# auto_turn.net
KiCad netlist of a schematic drawn in Altium Designer
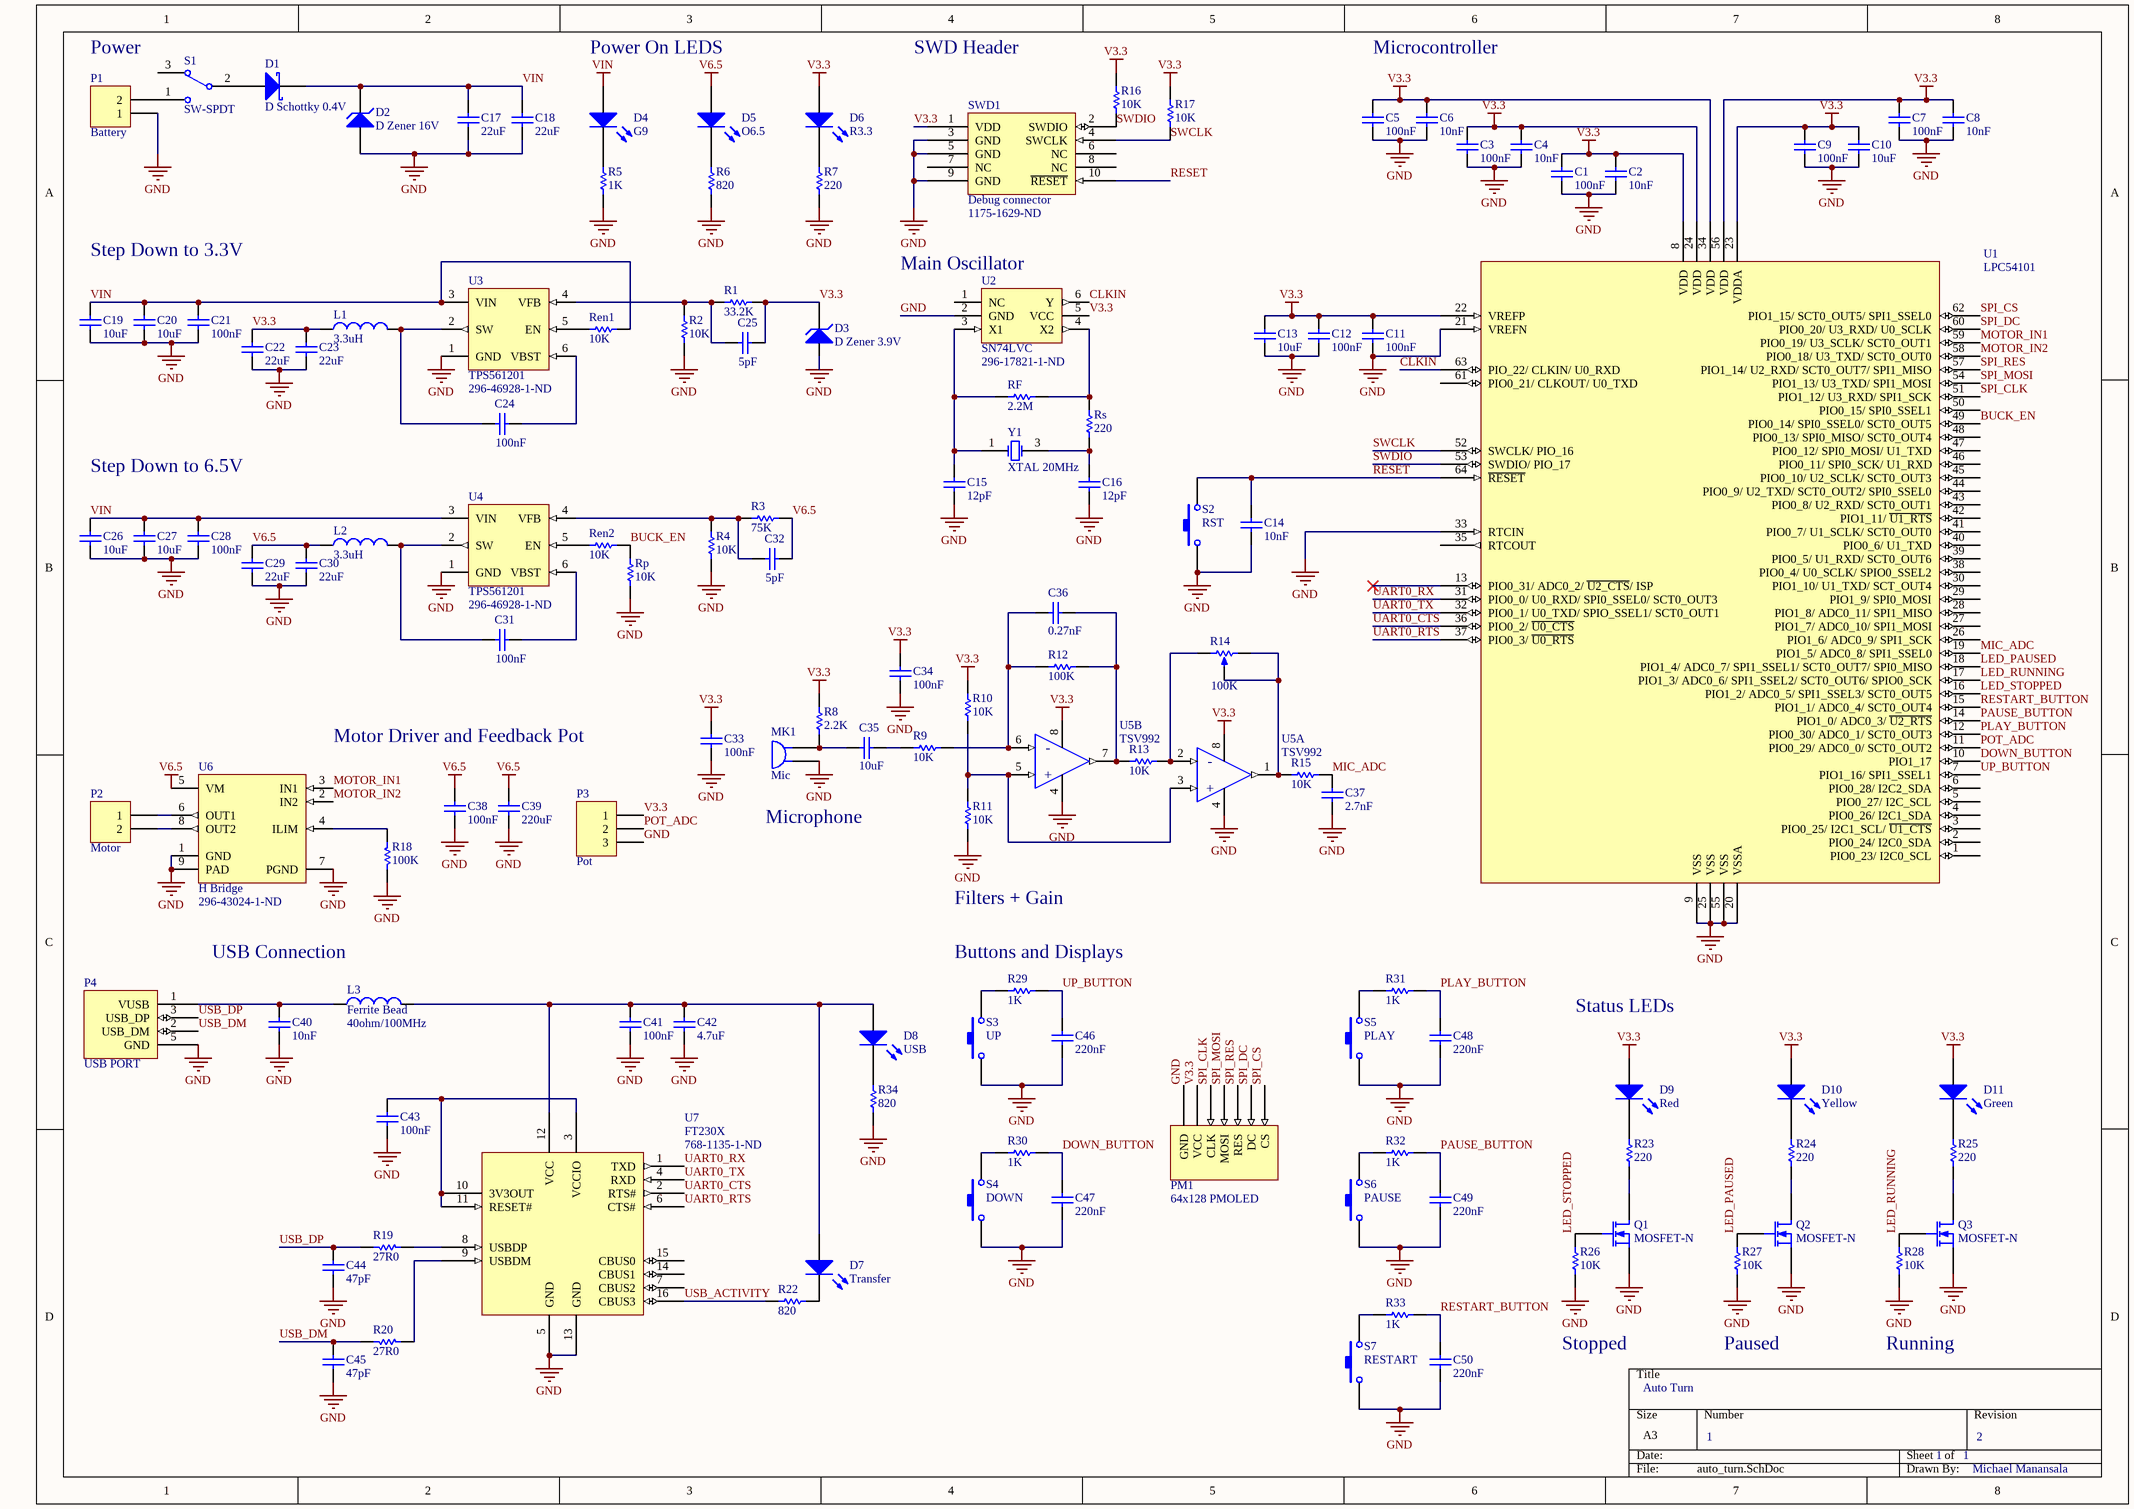
[diagram p0: auto_turn.SchDoc]

(export (version "E")
  (design (tool "Eeschema 10.0.6"))
  (components
    (comp (ref "C1")
      (value "100nF")
      (footprint "0805 MD")
      (description "Capacitor")
      (fields
        (field (name "MANUFACTURER") "Samsung Electro-Mechanics America, Inc.")
        (field (name "MANUFACTURERPARTNUMBER") "CL21B104JBCNNNC")
      )
      (libsource (lib "Miscellaneous Devices") (part "Cap"))
    )
    (comp (ref "C2")
      (value "10nF")
      (footprint "0805 MD")
      (description "Capacitor")
      (fields
        (field (name "MANUFACTURER") "Samsung Electro-Mechanics America, Inc.")
        (field (name "MANUFACTURERPARTNUMBER") "CL21B103JBANNNC")
      )
      (libsource (lib "Miscellaneous Devices") (part "Cap"))
    )
    (comp (ref "C3")
      (value "100nF")
      (footprint "0805 MD")
      (description "Capacitor")
      (fields
        (field (name "MANUFACTURER") "Samsung Electro-Mechanics America, Inc.")
        (field (name "MANUFACTURERPARTNUMBER") "CL21B104JBCNNNC")
      )
      (libsource (lib "Miscellaneous Devices") (part "Cap"))
    )
    (comp (ref "C4")
      (value "10nF")
      (footprint "0805 MD")
      (description "Capacitor")
      (fields
        (field (name "MANUFACTURER") "Samsung Electro-Mechanics America, Inc.")
        (field (name "MANUFACTURERPARTNUMBER") "CL21B103JBANNNC")
      )
      (libsource (lib "Miscellaneous Devices") (part "Cap"))
    )
    (comp (ref "C5")
      (value "100nF")
      (footprint "0805 MD")
      (description "Capacitor")
      (fields
        (field (name "MANUFACTURER") "Samsung Electro-Mechanics America, Inc.")
        (field (name "MANUFACTURERPARTNUMBER") "CL21B104JBCNNNC")
      )
      (libsource (lib "Miscellaneous Devices") (part "Cap"))
    )
    (comp (ref "C6")
      (value "10nF")
      (footprint "0805 MD")
      (description "Capacitor")
      (fields
        (field (name "MANUFACTURER") "Samsung Electro-Mechanics America, Inc.")
        (field (name "MANUFACTURERPARTNUMBER") "CL21B103JBANNNC")
      )
      (libsource (lib "Miscellaneous Devices") (part "Cap"))
    )
    (comp (ref "C7")
      (value "100nF")
      (footprint "0805 MD")
      (description "Capacitor")
      (fields
        (field (name "MANUFACTURER") "Samsung Electro-Mechanics America, Inc.")
        (field (name "MANUFACTURERPARTNUMBER") "CL21B104JBCNNNC")
      )
      (libsource (lib "Miscellaneous Devices") (part "Cap"))
    )
    (comp (ref "C8")
      (value "10nF")
      (footprint "0805 MD")
      (description "Capacitor")
      (fields
        (field (name "MANUFACTURER") "Samsung Electro-Mechanics America, Inc.")
        (field (name "MANUFACTURERPARTNUMBER") "CL21B103JBANNNC")
      )
      (libsource (lib "Miscellaneous Devices") (part "Cap"))
    )
    (comp (ref "C9")
      (value "100nF")
      (footprint "0805 MD")
      (description "Capacitor")
      (fields
        (field (name "MANUFACTURER") "Samsung Electro-Mechanics America, Inc.")
        (field (name "MANUFACTURERPARTNUMBER") "CL21B104JBCNNNC")
      )
      (libsource (lib "Miscellaneous Devices") (part "Cap"))
    )
    (comp (ref "C10")
      (value "10uF")
      (footprint "0805 MD")
      (description "Capacitor")
      (fields
        (field (name "MANUFACTURER") "Samsung Electro-Mechanics America, Inc.")
        (field (name "MANUFACTURERPARTNUMBER") "CL21A106KOCLRNC")
      )
      (libsource (lib "Miscellaneous Devices") (part "Cap"))
    )
    (comp (ref "C11")
      (value "100nF")
      (footprint "0805 MD")
      (description "Capacitor")
      (fields
        (field (name "MANUFACTURER") "Samsung Electro-Mechanics America, Inc.")
        (field (name "MANUFACTURERPARTNUMBER") "CL21B104JBCNNNC")
      )
      (libsource (lib "Miscellaneous Devices") (part "Cap"))
    )
    (comp (ref "C12")
      (value "100nF")
      (footprint "0805 MD")
      (description "Capacitor")
      (fields
        (field (name "MANUFACTURER") "Samsung Electro-Mechanics America, Inc.")
        (field (name "MANUFACTURERPARTNUMBER") "CL21B104JBCNNNC")
      )
      (libsource (lib "Miscellaneous Devices") (part "Cap"))
    )
    (comp (ref "C13")
      (value "10uF")
      (footprint "0805 MD")
      (description "Capacitor")
      (fields
        (field (name "MANUFACTURER") "Samsung Electro-Mechanics America, Inc.")
        (field (name "MANUFACTURERPARTNUMBER") "CL21A106KOCLRNC")
      )
      (libsource (lib "Miscellaneous Devices") (part "Cap"))
    )
    (comp (ref "C14")
      (value "10nF")
      (footprint "0805 MD")
      (description "Capacitor")
      (fields
        (field (name "MANUFACTURER") "Samsung Electro-Mechanics America, Inc.")
        (field (name "MANUFACTURERPARTNUMBER") "CL21B103JBANNNC")
      )
      (libsource (lib "Miscellaneous Devices") (part "Cap"))
    )
    (comp (ref "C15")
      (value "12pF")
      (footprint "0805 MD")
      (description "Capacitor")
      (fields
        (field (name "MANUFACTURER") "Samsung Electro-Mechanics America, Inc.")
        (field (name "MANUFACTURERPARTNUMBER") "CL21C120JBANNNC")
      )
      (libsource (lib "Miscellaneous Devices") (part "Cap"))
    )
    (comp (ref "C16")
      (value "12pF")
      (footprint "0805 MD")
      (description "Capacitor")
      (fields
        (field (name "MANUFACTURER") "Samsung Electro-Mechanics America, Inc.")
        (field (name "MANUFACTURERPARTNUMBER") "CL21C120JBANNNC")
      )
      (libsource (lib "Miscellaneous Devices") (part "Cap"))
    )
    (comp (ref "C17")
      (value "22uF")
      (footprint "0805 MD")
      (description "Capacitor")
      (fields
        (field (name "MANUFACTURER") "Samsung Electro-Mechanics America, Inc.")
        (field (name "MANUFACTURERPARTNUMBER") "CL21A226MOCLRNC")
      )
      (libsource (lib "Miscellaneous Devices") (part "Cap"))
    )
    (comp (ref "C18")
      (value "22uF")
      (footprint "0805 MD")
      (description "Capacitor")
      (fields
        (field (name "MANUFACTURER") "Samsung Electro-Mechanics America, Inc.")
        (field (name "MANUFACTURERPARTNUMBER") "CL21A226MOCLRNC")
      )
      (libsource (lib "Miscellaneous Devices") (part "Cap"))
    )
    (comp (ref "C19")
      (value "10uF")
      (footprint "0805 MD")
      (description "Capacitor")
      (fields
        (field (name "MANUFACTURER") "Samsung Electro-Mechanics America, Inc.")
        (field (name "MANUFACTURERPARTNUMBER") "CL21A106KOCLRNC")
      )
      (libsource (lib "Miscellaneous Devices") (part "Cap"))
    )
    (comp (ref "C20")
      (value "10uF")
      (footprint "0805 MD")
      (description "Capacitor")
      (fields
        (field (name "MANUFACTURER") "Samsung Electro-Mechanics America, Inc.")
        (field (name "MANUFACTURERPARTNUMBER") "CL21A106KOCLRNC")
      )
      (libsource (lib "Miscellaneous Devices") (part "Cap"))
    )
    (comp (ref "C21")
      (value "100nF")
      (footprint "0805 MD")
      (description "Capacitor")
      (fields
        (field (name "MANUFACTURER") "Samsung Electro-Mechanics America, Inc.")
        (field (name "MANUFACTURERPARTNUMBER") "CL21B104JBCNNNC")
      )
      (libsource (lib "Miscellaneous Devices") (part "Cap"))
    )
    (comp (ref "C22")
      (value "22uF")
      (footprint "0805 MD")
      (description "Capacitor")
      (fields
        (field (name "MANUFACTURER") "Samsung Electro-Mechanics America, Inc.")
        (field (name "MANUFACTURERPARTNUMBER") "CL21A226MOCLRNC")
      )
      (libsource (lib "Miscellaneous Devices") (part "Cap"))
    )
    (comp (ref "C23")
      (value "22uF")
      (footprint "0805 MD")
      (description "Capacitor")
      (fields
        (field (name "MANUFACTURER") "Samsung Electro-Mechanics America, Inc.")
        (field (name "MANUFACTURERPARTNUMBER") "CL21A226MOCLRNC")
      )
      (libsource (lib "Miscellaneous Devices") (part "Cap"))
    )
    (comp (ref "C24")
      (value "100nF")
      (footprint "0805 MD")
      (description "Capacitor")
      (fields
        (field (name "MANUFACTURER") "Samsung Electro-Mechanics America, Inc.")
        (field (name "MANUFACTURERPARTNUMBER") "CL21B104JBCNNNC")
      )
      (libsource (lib "Miscellaneous Devices") (part "Cap"))
    )
    (comp (ref "C25")
      (value "5pF")
      (footprint "0805 MD")
      (description "Capacitor")
      (fields
        (field (name "MANUFACTURER") "Samsung Electro-Mechanics America, Inc.")
        (field (name "MANUFACTURERPARTNUMBER") "CL21C050CBANNNC")
      )
      (libsource (lib "Miscellaneous Devices") (part "Cap"))
    )
    (comp (ref "C26")
      (value "10uF")
      (footprint "0805 MD")
      (description "Capacitor")
      (fields
        (field (name "MANUFACTURER") "Samsung Electro-Mechanics America, Inc.")
        (field (name "MANUFACTURERPARTNUMBER") "CL21A106KOCLRNC")
      )
      (libsource (lib "Miscellaneous Devices") (part "Cap"))
    )
    (comp (ref "C27")
      (value "10uF")
      (footprint "0805 MD")
      (description "Capacitor")
      (fields
        (field (name "MANUFACTURER") "Samsung Electro-Mechanics America, Inc.")
        (field (name "MANUFACTURERPARTNUMBER") "CL21A106KOCLRNC")
      )
      (libsource (lib "Miscellaneous Devices") (part "Cap"))
    )
    (comp (ref "C28")
      (value "100nF")
      (footprint "0805 MD")
      (description "Capacitor")
      (fields
        (field (name "MANUFACTURER") "Samsung Electro-Mechanics America, Inc.")
        (field (name "MANUFACTURERPARTNUMBER") "CL21B104JBCNNNC")
      )
      (libsource (lib "Miscellaneous Devices") (part "Cap"))
    )
    (comp (ref "C29")
      (value "22uF")
      (footprint "0805 MD")
      (description "Capacitor")
      (fields
        (field (name "MANUFACTURER") "Samsung Electro-Mechanics America, Inc.")
        (field (name "MANUFACTURERPARTNUMBER") "CL21A226MOCLRNC")
      )
      (libsource (lib "Miscellaneous Devices") (part "Cap"))
    )
    (comp (ref "C30")
      (value "22uF")
      (footprint "0805 MD")
      (description "Capacitor")
      (fields
        (field (name "MANUFACTURER") "Samsung Electro-Mechanics America, Inc.")
        (field (name "MANUFACTURERPARTNUMBER") "CL21A226MOCLRNC")
      )
      (libsource (lib "Miscellaneous Devices") (part "Cap"))
    )
    (comp (ref "C31")
      (value "100nF")
      (footprint "0805 MD")
      (description "Capacitor")
      (fields
        (field (name "MANUFACTURER") "Samsung Electro-Mechanics America, Inc.")
        (field (name "MANUFACTURERPARTNUMBER") "CL21B104JBCNNNC")
      )
      (libsource (lib "Miscellaneous Devices") (part "Cap"))
    )
    (comp (ref "C32")
      (value "5pF")
      (footprint "0805 MD")
      (description "Capacitor")
      (fields
        (field (name "MANUFACTURER") "Samsung Electro-Mechanics America, Inc.")
        (field (name "MANUFACTURERPARTNUMBER") "CL21C050CBANNNC")
      )
      (libsource (lib "Miscellaneous Devices") (part "Cap"))
    )
    (comp (ref "C33")
      (value "100nF")
      (footprint "0805 MD")
      (description "Capacitor")
      (fields
        (field (name "MANUFACTURER") "Samsung Electro-Mechanics America, Inc.")
        (field (name "MANUFACTURERPARTNUMBER") "CL21B104JBCNNNC")
      )
      (libsource (lib "Miscellaneous Devices") (part "Cap"))
    )
    (comp (ref "C34")
      (value "100nF")
      (footprint "0805 MD")
      (description "Capacitor")
      (fields
        (field (name "MANUFACTURER") "Samsung Electro-Mechanics America, Inc.")
        (field (name "MANUFACTURERPARTNUMBER") "CL21B104JBCNNNC")
      )
      (libsource (lib "Miscellaneous Devices") (part "Cap"))
    )
    (comp (ref "C35")
      (value "10uF")
      (footprint "0805 MD")
      (description "Capacitor")
      (fields
        (field (name "MANUFACTURER") "Samsung Electro-Mechanics America, Inc.")
        (field (name "MANUFACTURERPARTNUMBER") "CL21A106KOCLRNC")
      )
      (libsource (lib "Miscellaneous Devices") (part "Cap"))
    )
    (comp (ref "C36")
      (value "0.27nF")
      (footprint "0805 MD")
      (description "Capacitor")
      (fields
        (field (name "MANUFACTURER") "Samsung Electro-Mechanics America, Inc.")
        (field (name "MANUFACTURERPARTNUMBER") "CL21B271KCANNNC")
      )
      (libsource (lib "Miscellaneous Devices") (part "Cap"))
    )
    (comp (ref "C37")
      (value "2.7nF")
      (footprint "0805 MD")
      (description "Capacitor")
      (fields
        (field (name "MANUFACTURER") "Samsung Electro-Mechanics America, Inc.")
        (field (name "MANUFACTURERPARTNUMBER") "CL21C272JBFNNNE")
      )
      (libsource (lib "Miscellaneous Devices") (part "Cap"))
    )
    (comp (ref "C38")
      (value "100nF")
      (footprint "0805 MD")
      (description "Capacitor")
      (fields
        (field (name "MANUFACTURER") "Samsung Electro-Mechanics America, Inc.")
        (field (name "MANUFACTURERPARTNUMBER") "CL21B104JBCNNNC")
      )
      (libsource (lib "Miscellaneous Devices") (part "Cap"))
    )
    (comp (ref "C39")
      (value "220uF")
      (footprint "RAD-0.1")
      (description "Capacitor")
      (fields (field (name "MANUFACTURER") "Nichicon") (field (name "MANUFACTURERPARTNUMBER") "UVR1C221MED"))
      (libsource (lib "Miscellaneous Devices") (part "Cap"))
    )
    (comp (ref "C40")
      (value "10nF")
      (footprint "0805 MD")
      (description "Capacitor")
      (fields
        (field (name "MANUFACTURER") "Samsung Electro-Mechanics America, Inc.")
        (field (name "MANUFACTURERPARTNUMBER") "CL21B103JBANNNC")
      )
      (libsource (lib "Miscellaneous Devices") (part "Cap"))
    )
    (comp (ref "C41")
      (value "100nF")
      (footprint "0805 MD")
      (description "Capacitor")
      (fields
        (field (name "MANUFACTURER") "Samsung Electro-Mechanics America, Inc.")
        (field (name "MANUFACTURERPARTNUMBER") "CL21B104JBCNNNC")
      )
      (libsource (lib "Miscellaneous Devices") (part "Cap"))
    )
    (comp (ref "C42")
      (value "4.7uF")
      (footprint "0805 MD")
      (description "Capacitor")
      (fields
        (field (name "MANUFACTURER") "Samsung Electro-Mechanics America, Inc.")
        (field (name "MANUFACTURERPARTNUMBER") "CL21A475KQFNNNG")
      )
      (libsource (lib "Miscellaneous Devices") (part "Cap"))
    )
    (comp (ref "C43")
      (value "100nF")
      (footprint "0805 MD")
      (description "Capacitor")
      (fields
        (field (name "MANUFACTURER") "Samsung Electro-Mechanics America, Inc.")
        (field (name "MANUFACTURERPARTNUMBER") "CL21B104JBCNNNC")
      )
      (libsource (lib "Miscellaneous Devices") (part "Cap"))
    )
    (comp (ref "C44")
      (value "47pF")
      (footprint "0805 MD")
      (description "Capacitor")
      (fields
        (field (name "MANUFACTURER") "Samsung Electro-Mechanics America, Inc.")
        (field (name "MANUFACTURERPARTNUMBER") "CL21C470JBANNNC")
      )
      (libsource (lib "Miscellaneous Devices") (part "Cap"))
    )
    (comp (ref "C45")
      (value "47pF")
      (footprint "0805 MD")
      (description "Capacitor")
      (fields
        (field (name "MANUFACTURER") "Samsung Electro-Mechanics America, Inc.")
        (field (name "MANUFACTURERPARTNUMBER") "CL21C470JBANNNC")
      )
      (libsource (lib "Miscellaneous Devices") (part "Cap"))
    )
    (comp (ref "C46")
      (value "220nF")
      (footprint "0805 MD")
      (description "Capacitor")
      (fields
        (field (name "MANUFACTURER") "Samsung Electro-Mechanics America, Inc.")
        (field (name "MANUFACTURERPARTNUMBER") "CL21B224KAFNNNG")
      )
      (libsource (lib "Miscellaneous Devices") (part "Cap"))
    )
    (comp (ref "C47")
      (value "220nF")
      (footprint "0805 MD")
      (description "Capacitor")
      (fields
        (field (name "MANUFACTURER") "Samsung Electro-Mechanics America, Inc.")
        (field (name "MANUFACTURERPARTNUMBER") "CL21B224KAFNNNG")
      )
      (libsource (lib "Miscellaneous Devices") (part "Cap"))
    )
    (comp (ref "C48")
      (value "220nF")
      (footprint "0805 MD")
      (description "Capacitor")
      (fields
        (field (name "MANUFACTURER") "Samsung Electro-Mechanics America, Inc.")
        (field (name "MANUFACTURERPARTNUMBER") "CL21B224KAFNNNG")
      )
      (libsource (lib "Miscellaneous Devices") (part "Cap"))
    )
    (comp (ref "C49")
      (value "220nF")
      (footprint "0805 MD")
      (description "Capacitor")
      (fields
        (field (name "MANUFACTURER") "Samsung Electro-Mechanics America, Inc.")
        (field (name "MANUFACTURERPARTNUMBER") "CL21B224KAFNNNG")
      )
      (libsource (lib "Miscellaneous Devices") (part "Cap"))
    )
    (comp (ref "C50")
      (value "220nF")
      (footprint "0805 MD")
      (description "Capacitor")
      (fields
        (field (name "MANUFACTURER") "Samsung Electro-Mechanics America, Inc.")
        (field (name "MANUFACTURERPARTNUMBER") "CL21B224KAFNNNG")
      )
      (libsource (lib "Miscellaneous Devices") (part "Cap"))
    )
    (comp (ref "D1")
      (value "D Schottky 0.4V")
      (footprint "DO219AB")
      (description "Schottky Diode")
      (fields
        (field (name "MANUFACTURER") "Vishay Semiconductor Diodes Division")
        (field (name "MANUFACTURERPARTNUMBER") "SL02-GS08")
      )
      (libsource (lib "Miscellaneous Devices") (part "D Schottky"))
    )
    (comp (ref "D2")
      (value "D Zener 16V")
      (footprint "DO219AB")
      (description "Zener Diode")
      (fields
        (field (name "MANUFACTURER") "Vishay Semiconductor Diodes Division")
        (field (name "MANUFACTURERPARTNUMBER") "BZD27C16P-E3-08")
      )
      (libsource (lib "Miscellaneous Devices") (part "D Zener"))
    )
    (comp (ref "D3")
      (value "D Zener 3.9V")
      (footprint "DO219AB")
      (description "Zener Diode")
      (fields
        (field (name "MANUFACTURER") "Vishay Semiconductor Diodes Division")
        (field (name "MANUFACTURERPARTNUMBER") "BZD27B3V9P-M3-08")
      )
      (libsource (lib "Miscellaneous Devices") (part "D Zener"))
    )
    (comp (ref "D4")
      (value "G9")
      (footprint "0805 MD")
      (description "LED Green")
      (fields
        (field (name "MANUFACTURER") "Lite-On Inc.")
        (field (name "MANUFACTURERPARTNUMBER") "LTST-C171KGKT")
      )
      (libsource (lib "Miscellaneous Devices") (part "LED1"))
    )
    (comp (ref "D5")
      (value "O6.5")
      (footprint "0805 MD")
      (description "LED Orange")
      (fields
        (field (name "MANUFACTURER") "Lite-On Inc.")
        (field (name "MANUFACTURERPARTNUMBER") "LTST-C170KFKT")
      )
      (libsource (lib "Miscellaneous Devices") (part "LED1"))
    )
    (comp (ref "D6")
      (value "R3.3")
      (footprint "0805 MD")
      (description "LED Red")
      (fields
        (field (name "MANUFACTURER") "Lite-On Inc.")
        (field (name "MANUFACTURERPARTNUMBER") "LTST-C171KRKT")
      )
      (libsource (lib "Miscellaneous Devices") (part "LED1"))
    )
    (comp (ref "D7")
      (value "Transfer")
      (footprint "0805 MD")
      (description "Green LED")
      (fields
        (field (name "MANUFACTURER") "Lite-On Inc.")
        (field (name "MANUFACTURERPARTNUMBER") "LTST-C171KRKT")
      )
      (libsource (lib "Miscellaneous Devices") (part "LED1"))
    )
    (comp (ref "D8")
      (value "USB")
      (footprint "0805 MD")
      (description "LED Green")
      (fields
        (field (name "MANUFACTURER") "Lite-On Inc.")
        (field (name "MANUFACTURERPARTNUMBER") "LTST-C171KGKT")
      )
      (libsource (lib "Miscellaneous Devices") (part "LED1"))
    )
    (comp (ref "D9")
      (value "Red")
      (footprint "5mm LED")
      (description "LED Red")
      (fields (field (name "MANUFACTURER") "Kingbright") (field (name "MANUFACTURERPARTNUMBER") "WP7113ID"))
      (libsource (lib "Miscellaneous Devices") (part "LED1"))
    )
    (comp (ref "D10")
      (value "Yellow")
      (footprint "5mm LED")
      (description "LED Yellow")
      (fields (field (name "MANUFACTURER") "Kingbright") (field (name "MANUFACTURERPARTNUMBER") "WP7113ND"))
      (libsource (lib "Miscellaneous Devices") (part "LED1"))
    )
    (comp (ref "D11")
      (value "Green")
      (footprint "5mm LED")
      (description "LED Green")
      (fields (field (name "MANUFACTURER") "Kingbright") (field (name "MANUFACTURERPARTNUMBER") "WP7113GD"))
      (libsource (lib "Miscellaneous Devices") (part "LED1"))
    )
    (comp (ref "L1")
      (value "3.3uH")
      (footprint "0805 MD")
      (description "Inductor")
      (fields
        (field (name "MANUFACTURER") "Taiyo Yuden")
        (field (name "MANUFACTURERPARTNUMBER") "BRC2012T3R3MD")
      )
      (libsource (lib "Miscellaneous Devices") (part "Inductor"))
    )
    (comp (ref "L2")
      (value "3.3uH")
      (footprint "0805 MD")
      (description "Inductor")
      (fields
        (field (name "MANUFACTURER") "Taiyo Yuden")
        (field (name "MANUFACTURERPARTNUMBER") "BRC2012T3R3MD")
      )
      (libsource (lib "Miscellaneous Devices") (part "Inductor"))
    )
    (comp (ref "L3")
      (value "Ferrite Bead")
      (footprint "0805 MD")
      (description "Inductor")
      (fields
        (field (name "ALTIUM_VALUE") "40ohm/100MHz")
        (field (name "MANUFACTURER") "Laird-Signal Integrity Products")
        (field (name "MANUFACTURERPARTNUMBER") "MI0805K400R-10")
      )
      (libsource (lib "Miscellaneous Devices") (part "Inductor"))
    )
    (comp (ref "MK1")
      (value "Mic")
      (footprint "CMA-4544PF-W")
      (description "Electret Microphone")
      (fields (field (name "MANUFACTURER") "CUI Inc.") (field (name "MANUFACTURERPARTNUMBER") "CMA-4544PF-W"))
      (libsource (lib "Miscellaneous Devices") (part "Mic1"))
    )
    (comp (ref "P1")
      (value "Battery")
      (footprint "HDR1X2")
      (description "Header, 2-Pin")
      (libsource (lib "") (part "Header 2_1"))
    )
    (comp (ref "P2")
      (value "Motor")
      (footprint "HDR1X2")
      (description "Header, 2-Pin")
      (fields (field (name "MANUFACTURER") "DFRobot") (field (name "MANUFACTURERPARTNUMBER") "FIT0495-E"))
      (libsource (lib "Miscellaneous Connectors") (part "Header 2"))
    )
    (comp (ref "P3")
      (value "Pot")
      (footprint "HDR1X3")
      (description "Header, 3-Pin")
      (fields
        (field (name "MANUFACTURER") "Bourns Inc.")
        (field (name "MANUFACTURERPARTNUMBER") "PDB241-E420P-103B0")
      )
      (libsource (lib "Miscellaneous Connectors") (part "Header 3"))
    )
    (comp (ref "P4")
      (value "USB PORT")
      (footprint "USB Micro B")
      (description "USB port")
      (fields
        (field (name "MANUFACTURER") "Amphenol FCI")
        (field (name "MANUFACTURERPARTNUMBER") "10118192-0001LF")
      )
      (libsource (lib "auto_turn_components") (part "USB PORT"))
    )
    (comp (ref "PM1")
      (value "64x128 PMOLED")
      (footprint "PMOLED 128x64")
      (description "Passive Matrix Organic LED Display")
      (libsource (lib "auto_turn_components") (part "PMOLED"))
    )
    (comp (ref "Q1")
      (value "MOSFET-N")
      (footprint "SOT23")
      (description "DMN2005K-7DICT-ND")
      (fields
        (field (name "MANUFACTURER") "Diodes Incorporated")
        (field (name "MANUFACTURERPARTNUMBER") "DMN2005K-7")
      )
      (libsource (lib "Miscellaneous Devices") (part "MOSFET-N"))
    )
    (comp (ref "Q2")
      (value "MOSFET-N")
      (footprint "SOT23")
      (description "DMN2005K-7DICT-ND")
      (fields
        (field (name "MANUFACTURER") "Diodes Incorporated")
        (field (name "MANUFACTURERPARTNUMBER") "DMN2005K-7")
      )
      (libsource (lib "Miscellaneous Devices") (part "MOSFET-N"))
    )
    (comp (ref "Q3")
      (value "MOSFET-N")
      (footprint "SOT23")
      (description "DMN2005K-7DICT-ND")
      (fields
        (field (name "MANUFACTURER") "Diodes Incorporated")
        (field (name "MANUFACTURERPARTNUMBER") "DMN2005K-7")
      )
      (libsource (lib "Miscellaneous Devices") (part "MOSFET-N"))
    )
    (comp (ref "R1")
      (value "33.2K")
      (footprint "0805 MD")
      (description "Resistor")
      (fields
        (field (name "MANUFACTURER") "Stackpole Electronics")
        (field (name "MANUFACTURERPARTNUMBER") "RMCF0805FT33K2")
      )
      (libsource (lib "Miscellaneous Devices") (part "Res1"))
    )
    (comp (ref "R2")
      (value "10K")
      (footprint "0805 MD")
      (description "Resistor")
      (fields
        (field (name "MANUFACTURER") "Stackpole Electronics")
        (field (name "MANUFACTURERPARTNUMBER") "RMCF0805FT10K0")
      )
      (libsource (lib "Miscellaneous Devices") (part "Res1"))
    )
    (comp (ref "R3")
      (value "75K")
      (footprint "0805 MD")
      (description "Resistor")
      (fields
        (field (name "MANUFACTURER") "Stackpole Electronics")
        (field (name "MANUFACTURERPARTNUMBER") "RMCF0805FT75K0")
      )
      (libsource (lib "Miscellaneous Devices") (part "Res1"))
    )
    (comp (ref "R4")
      (value "10K")
      (footprint "0805 MD")
      (description "Resistor")
      (fields
        (field (name "MANUFACTURER") "Stackpole Electronics")
        (field (name "MANUFACTURERPARTNUMBER") "RMCF0805FT10K0")
      )
      (libsource (lib "Miscellaneous Devices") (part "Res1"))
    )
    (comp (ref "R5")
      (value "1K")
      (footprint "0805 MD")
      (description "Resistor")
      (fields
        (field (name "MANUFACTURER") "Stackpole Electronics")
        (field (name "MANUFACTURERPARTNUMBER") "RMCF0805FT1K00")
      )
      (libsource (lib "Miscellaneous Devices") (part "Res1"))
    )
    (comp (ref "R6")
      (value "820")
      (footprint "0805 MD")
      (description "Resistor")
      (fields
        (field (name "MANUFACTURER") "Stackpole Electronics")
        (field (name "MANUFACTURERPARTNUMBER") "RMCF0805FT820R")
      )
      (libsource (lib "Miscellaneous Devices") (part "Res1"))
    )
    (comp (ref "R7")
      (value "220")
      (footprint "0805 MD")
      (description "Resistor")
      (fields
        (field (name "MANUFACTURER") "Stackpole Electronics")
        (field (name "MANUFACTURERPARTNUMBER") "RMCF0805FT220R")
      )
      (libsource (lib "Miscellaneous Devices") (part "Res1"))
    )
    (comp (ref "R8")
      (value "2.2K")
      (footprint "0805 MD")
      (description "Resistor")
      (fields
        (field (name "MANUFACTURER") "Stackpole Electronics")
        (field (name "MANUFACTURERPARTNUMBER") "RMCF0805FT2K20")
      )
      (libsource (lib "Miscellaneous Devices") (part "Res1"))
    )
    (comp (ref "R9")
      (value "10K")
      (footprint "0805 MD")
      (description "Resistor")
      (fields
        (field (name "MANUFACTURER") "Stackpole Electronics")
        (field (name "MANUFACTURERPARTNUMBER") "RMCF0805FT10K0")
      )
      (libsource (lib "Miscellaneous Devices") (part "Res1"))
    )
    (comp (ref "R10")
      (value "10K")
      (footprint "0805 MD")
      (description "Resistor")
      (fields
        (field (name "MANUFACTURER") "Stackpole Electronics")
        (field (name "MANUFACTURERPARTNUMBER") "RMCF0805FT10K0")
      )
      (libsource (lib "Miscellaneous Devices") (part "Res1"))
    )
    (comp (ref "R11")
      (value "10K")
      (footprint "0805 MD")
      (description "Resistor")
      (fields
        (field (name "MANUFACTURER") "Stackpole Electronics")
        (field (name "MANUFACTURERPARTNUMBER") "RMCF0805FT10K0")
      )
      (libsource (lib "Miscellaneous Devices") (part "Res1"))
    )
    (comp (ref "R12")
      (value "100K")
      (footprint "0805 MD")
      (description "Resistor")
      (fields
        (field (name "MANUFACTURER") "Stackpole Electronics")
        (field (name "MANUFACTURERPARTNUMBER") "RMCF0805FT100K")
      )
      (libsource (lib "Miscellaneous Devices") (part "Res1"))
    )
    (comp (ref "R13")
      (value "10K")
      (footprint "0805 MD")
      (description "Resistor")
      (fields
        (field (name "MANUFACTURER") "Stackpole Electronics")
        (field (name "MANUFACTURERPARTNUMBER") "RMCF0805FT10K0")
      )
      (libsource (lib "Miscellaneous Devices") (part "Res1"))
    )
    (comp (ref "R14")
      (value "100K")
      (footprint "Trimmer 23B")
      (description "Potentiometer")
      (fields
        (field (name "MANUFACTURER") "TT Electronics/BI")
        (field (name "MANUFACTURERPARTNUMBER") "23BR100KLFTR")
      )
      (libsource (lib "Miscellaneous Devices") (part "RPot"))
    )
    (comp (ref "R15")
      (value "10K")
      (footprint "0805 MD")
      (description "Resistor")
      (fields
        (field (name "MANUFACTURER") "Stackpole Electronics")
        (field (name "MANUFACTURERPARTNUMBER") "RMCF0805FT10K0")
      )
      (libsource (lib "Miscellaneous Devices") (part "Res1"))
    )
    (comp (ref "R16")
      (value "10K")
      (footprint "0805 MD")
      (description "Resistor")
      (fields
        (field (name "MANUFACTURER") "Stackpole Electronics")
        (field (name "MANUFACTURERPARTNUMBER") "RMCF0805FT10K0")
      )
      (libsource (lib "Miscellaneous Devices") (part "Res1"))
    )
    (comp (ref "R17")
      (value "10K")
      (footprint "0805 MD")
      (description "Resistor")
      (fields
        (field (name "MANUFACTURER") "Stackpole Electronics")
        (field (name "MANUFACTURERPARTNUMBER") "RMCF0805FT10K0")
      )
      (libsource (lib "Miscellaneous Devices") (part "Res1"))
    )
    (comp (ref "R18")
      (value "100K")
      (footprint "0805 MD")
      (description "Resistor")
      (fields
        (field (name "MANUFACTURER") "Stackpole Electronics")
        (field (name "MANUFACTURERPARTNUMBER") "RMCF0805FT100K")
      )
      (libsource (lib "Miscellaneous Devices") (part "Res1"))
    )
    (comp (ref "R19")
      (value "27R0")
      (footprint "0805 MD")
      (description "Resistor")
      (fields
        (field (name "MANUFACTURER") "Stackpole Electronics")
        (field (name "MANUFACTURERPARTNUMBER") "RMCF0805FT27R0")
      )
      (libsource (lib "Miscellaneous Devices") (part "Res1"))
    )
    (comp (ref "R20")
      (value "27R0")
      (footprint "0805 MD")
      (description "Resistor")
      (fields
        (field (name "MANUFACTURER") "Stackpole Electronics")
        (field (name "MANUFACTURERPARTNUMBER") "RMCF0805FT27R0")
      )
      (libsource (lib "Miscellaneous Devices") (part "Res1"))
    )
    (comp (ref "R22")
      (value "820")
      (footprint "0805 MD")
      (description "Resistor")
      (fields
        (field (name "MANUFACTURER") "Stackpole Electronics")
        (field (name "MANUFACTURERPARTNUMBER") "RMCF0805FT820R")
      )
      (libsource (lib "Miscellaneous Devices") (part "Res1"))
    )
    (comp (ref "R23")
      (value "220")
      (footprint "0805 MD")
      (description "Resistor")
      (fields
        (field (name "MANUFACTURER") "Stackpole Electronics")
        (field (name "MANUFACTURERPARTNUMBER") "RMCF0805FT220R")
      )
      (libsource (lib "Miscellaneous Devices") (part "Res1"))
    )
    (comp (ref "R24")
      (value "220")
      (footprint "0805 MD")
      (description "Resistor")
      (fields
        (field (name "MANUFACTURER") "Stackpole Electronics")
        (field (name "MANUFACTURERPARTNUMBER") "RMCF0805FT220R")
      )
      (libsource (lib "Miscellaneous Devices") (part "Res1"))
    )
    (comp (ref "R25")
      (value "220")
      (footprint "0805 MD")
      (description "Resistor")
      (fields
        (field (name "MANUFACTURER") "Stackpole Electronics")
        (field (name "MANUFACTURERPARTNUMBER") "RMCF0805FT220R")
      )
      (libsource (lib "Miscellaneous Devices") (part "Res1"))
    )
    (comp (ref "R26")
      (value "10K")
      (footprint "0805 MD")
      (description "Resistor")
      (fields
        (field (name "MANUFACTURER") "Stackpole Electronics")
        (field (name "MANUFACTURERPARTNUMBER") "RMCF0805FT10K0")
      )
      (libsource (lib "Miscellaneous Devices") (part "Res1"))
    )
    (comp (ref "R27")
      (value "10K")
      (footprint "0805 MD")
      (description "Resistor")
      (fields
        (field (name "MANUFACTURER") "Stackpole Electronics")
        (field (name "MANUFACTURERPARTNUMBER") "RMCF0805FT10K0")
      )
      (libsource (lib "Miscellaneous Devices") (part "Res1"))
    )
    (comp (ref "R28")
      (value "10K")
      (footprint "0805 MD")
      (description "Resistor")
      (fields
        (field (name "MANUFACTURER") "Stackpole Electronics")
        (field (name "MANUFACTURERPARTNUMBER") "RMCF0805FT10K0")
      )
      (libsource (lib "Miscellaneous Devices") (part "Res1"))
    )
    (comp (ref "R29")
      (value "1K")
      (footprint "0805 MD")
      (description "Resistor")
      (fields
        (field (name "MANUFACTURER") "Stackpole Electronics")
        (field (name "MANUFACTURERPARTNUMBER") "RMCF0805FT1K00")
      )
      (libsource (lib "Miscellaneous Devices") (part "Res1"))
    )
    (comp (ref "R30")
      (value "1K")
      (footprint "0805 MD")
      (description "Resistor")
      (fields
        (field (name "MANUFACTURER") "Stackpole Electronics")
        (field (name "MANUFACTURERPARTNUMBER") "RMCF0805FT1K00")
      )
      (libsource (lib "Miscellaneous Devices") (part "Res1"))
    )
    (comp (ref "R31")
      (value "1K")
      (footprint "0805 MD")
      (description "Resistor")
      (fields
        (field (name "MANUFACTURER") "Stackpole Electronics")
        (field (name "MANUFACTURERPARTNUMBER") "RMCF0805FT1K00")
      )
      (libsource (lib "Miscellaneous Devices") (part "Res1"))
    )
    (comp (ref "R32")
      (value "1K")
      (footprint "0805 MD")
      (description "Resistor")
      (fields
        (field (name "MANUFACTURER") "Stackpole Electronics")
        (field (name "MANUFACTURERPARTNUMBER") "RMCF0805FT1K00")
      )
      (libsource (lib "Miscellaneous Devices") (part "Res1"))
    )
    (comp (ref "R33")
      (value "1K")
      (footprint "0805 MD")
      (description "Resistor")
      (fields
        (field (name "MANUFACTURER") "Stackpole Electronics")
        (field (name "MANUFACTURERPARTNUMBER") "RMCF0805FT1K00")
      )
      (libsource (lib "Miscellaneous Devices") (part "Res1"))
    )
    (comp (ref "R34")
      (value "820")
      (footprint "0805 MD")
      (description "Resistor")
      (fields
        (field (name "MANUFACTURER") "Stackpole Electronics")
        (field (name "MANUFACTURERPARTNUMBER") "RMCF0805FT820R")
      )
      (libsource (lib "Miscellaneous Devices") (part "Res1"))
    )
    (comp (ref "Ren1")
      (value "10K")
      (footprint "0805 MD")
      (description "Resistor")
      (fields
        (field (name "MANUFACTURER") "Stackpole Electronics")
        (field (name "MANUFACTURERPARTNUMBER") "RMCF0805FT10K0")
      )
      (libsource (lib "Miscellaneous Devices") (part "Res1"))
    )
    (comp (ref "Ren2")
      (value "10K")
      (footprint "0805 MD")
      (description "Resistor")
      (fields
        (field (name "MANUFACTURER") "Stackpole Electronics")
        (field (name "MANUFACTURERPARTNUMBER") "RMCF0805FT10K0")
      )
      (libsource (lib "Miscellaneous Devices") (part "Res1"))
    )
    (comp (ref "RF")
      (value "2.2M")
      (footprint "0805 MD")
      (description "Resistor")
      (fields
        (field (name "MANUFACTURER") "Stackpole Electronics")
        (field (name "MANUFACTURERPARTNUMBER") "RMCF0805JT2M20")
      )
      (libsource (lib "Miscellaneous Devices") (part "Res1"))
    )
    (comp (ref "Rp")
      (value "10K")
      (footprint "0805 MD")
      (description "Resistor")
      (fields
        (field (name "MANUFACTURER") "Stackpole Electronics")
        (field (name "MANUFACTURERPARTNUMBER") "RMCF0805FT10K0")
      )
      (libsource (lib "Miscellaneous Devices") (part "Res1"))
    )
    (comp (ref "Rs")
      (value "220")
      (footprint "0805 MD")
      (description "Resistor")
      (fields
        (field (name "MANUFACTURER") "Stackpole Electronics")
        (field (name "MANUFACTURERPARTNUMBER") "RMCF0805FT220R")
      )
      (libsource (lib "Miscellaneous Devices") (part "Res1"))
    )
    (comp (ref "S1")
      (value "SW-SPDT")
      (footprint "MFS101D-8-Z")
      (fields
        (field (name "MANUFACTURER") "Copal Electronics Inc.")
        (field (name "MANUFACTURERPARTNUMBER") "MFS101D-8-Z")
      )
      (libsource (lib "Miscellaneous Devices") (part "SW-SPDT"))
    )
    (comp (ref "S2")
      (value "RST")
      (footprint "Pushbutton KMR2")
      (description "Switch")
      (fields (field (name "MANUFACTURER") "C&K") (field (name "MANUFACTURERPARTNUMBER") "KMR231NG LFS"))
      (libsource (lib "Miscellaneous Devices") (part "SW-PB"))
    )
    (comp (ref "S3")
      (value "UP")
      (footprint "Pushbutton KMR2")
      (description "Switch")
      (fields (field (name "MANUFACTURER") "C&K") (field (name "MANUFACTURERPARTNUMBER") "KMR231NG LFS"))
      (libsource (lib "Miscellaneous Devices") (part "SW-PB"))
    )
    (comp (ref "S4")
      (value "DOWN")
      (footprint "Pushbutton KMR2")
      (description "Switch")
      (fields (field (name "MANUFACTURER") "C&K") (field (name "MANUFACTURERPARTNUMBER") "KMR231NG LFS"))
      (libsource (lib "Miscellaneous Devices") (part "SW-PB"))
    )
    (comp (ref "S5")
      (value "PLAY")
      (footprint "Pushbutton KMR2")
      (description "Switch")
      (fields (field (name "MANUFACTURER") "C&K") (field (name "MANUFACTURERPARTNUMBER") "KMR231NG LFS"))
      (libsource (lib "Miscellaneous Devices") (part "SW-PB"))
    )
    (comp (ref "S6")
      (value "PAUSE")
      (footprint "Pushbutton KMR2")
      (description "Switch")
      (fields (field (name "MANUFACTURER") "C&K") (field (name "MANUFACTURERPARTNUMBER") "KMR231NG LFS"))
      (libsource (lib "Miscellaneous Devices") (part "SW-PB"))
    )
    (comp (ref "S7")
      (value "RESTART")
      (footprint "Pushbutton KMR2")
      (description "Switch")
      (fields (field (name "MANUFACTURER") "C&K") (field (name "MANUFACTURERPARTNUMBER") "KMR231NG LFS"))
      (libsource (lib "Miscellaneous Devices") (part "SW-PB"))
    )
    (comp (ref "SWD1")
      (value "Debug connector")
      (footprint "ARM SWD connector")
      (description "ARM 10 pin SWD connecttor")
      (fields
        (field (name "SUPPLIER PART NUMBER 1") "1175-1629-ND")
        (field (name "MANUFACTURER") "CNC Tech")
        (field (name "MANUFACTURERPARTNUMBER") "3220-10-0300-00")
      )
      (libsource (lib "auto_turn_components") (part "Debug connector"))
    )
    (comp (ref "U1")
      (value "LPC54101")
      (footprint "LQFP64")
      (description "LPC54101 uC 64 pin")
      (fields
        (field (name "MANUFACTURERPARTNUMBER") "LPC54101J256BD64QL")
        (field (name "MANUFACTURER") "NXP")
      )
      (libsource (lib "auto_turn_components") (part "LPC54101"))
    )
    (comp (ref "U2")
      (value "SN74LVC")
      (footprint "SOT236")
      (description "Crystal Oscillator Driver IC SOT-23-6")
      (fields
        (field (name "MANUFACTURERPARTNUMBER") "SN74LVC1GX04DBVR")
        (field (name "MANUFACTURER") "Texas Instruments")
        (field (name "SUPPLIER PART NUMBER 1") "296-17821-1-ND")
      )
      (libsource (lib "auto_turn_components") (part "SN74LVC1GX04"))
    )
    (comp (ref "U3")
      (value "TPS561201")
      (footprint "SOT236")
      (description "Buck Regulator")
      (fields
        (field (name "MANUFACTURER") "Texas Instruments")
        (field (name "MANUFACTURERPARTNUMBER") "TPS561201DDCT")
        (field (name "SUPPLIER PART NUMBER 1") "296-46928-1-ND")
      )
      (libsource (lib "auto_turn_components") (part "TPS561201"))
    )
    (comp (ref "U4")
      (value "TPS561201")
      (footprint "SOT236")
      (description "Buck Regulator")
      (fields
        (field (name "MANUFACTURER") "Texas Instruments")
        (field (name "MANUFACTURERPARTNUMBER") "TPS561201DDCT")
        (field (name "SUPPLIER PART NUMBER 1") "296-46928-1-ND")
      )
      (libsource (lib "auto_turn_components") (part "TPS561201"))
    )
    (comp (ref "U5")
      (value "TSV992")
      (footprint "SOIC-8")
      (description "Dual Op Amp")
      (fields
        (field (name "MANUFACTURERPARTNUMBER") "TSV992IYDT")
        (field (name "MANUFACTURER") "ST Electronics")
      )
      (libsource (lib "auto_turn_components") (part "TSV992"))
    )
    (comp (ref "U6")
      (value "H Bridge")
      (footprint "SOIC-8 PP")
      (description "Half Bridge DC Motor Driver")
      (fields
        (field (name "MANUFACTURER") "Texas Instruments")
        (field (name "MANUFACTURERPARTNUMBER") "DRV8871DDAR")
        (field (name "SUPPLIER PART NUMBER 1") "296-43024-1-ND")
      )
      (libsource (lib "auto_turn_components") (part "DRV8871"))
    )
    (comp (ref "U7")
      (value "FT230X")
      (footprint "SSOP-16 FTDI")
      (description "FT230X USB TO BASIC UART IC")
      (fields (field (name "MANUFACTURER") "FTDI") (field (name "SUPPLIER PART NUMBER 1") "768-1135-1-ND"))
      (libsource (lib "auto_turn_components") (part "FT230X"))
    )
    (comp (ref "Y1")
      (value "XTAL 20MHz")
      (footprint "SMD XTAL 4Pin")
      (description "Crystal Oscillator")
      (fields
        (field (name "MANUFACTURER") "Abracon LLC")
        (field (name "MANUFACTURERPARTNUMBER") "ABM3B-20.000MHZ-10-1-U-T")
      )
      (libsource (lib "Miscellaneous Devices") (part "XTAL"))
    )
  )
  (nets
    (net (code "1") (name "/BUCK_EN") (class "Default")
      (node (ref "Ren2") (pin "2") (pinfunction "2_2") (pintype "passive"))
      (node (ref "Rp") (pin "2") (pinfunction "2_2") (pintype "passive"))
      (node (ref "U1") (pin "49") (pinfunction "PIO0_14/_SPI0_SSEL0/_SCT0_OUT5_49") (pintype "bidirectional"))
    )
    (net (code "2") (name "/CLKIN") (class "Default")
      (node (ref "U1") (pin "63") (pinfunction "PIO_22/_CLKIN/_U0_RXD_63") (pintype "bidirectional"))
      (node (ref "U2") (pin "6") (pinfunction "Y_6") (pintype "output"))
    )
    (net (code "3") (name "/DOWN_BUTTON") (class "Default")
      (node (ref "C47") (pin "2") (pinfunction "2_2") (pintype "passive"))
      (node (ref "R30") (pin "1") (pinfunction "1_1") (pintype "passive"))
      (node (ref "U1") (pin "10") (pinfunction "PIO1_17_10") (pintype "bidirectional"))
    )
    (net (code "4") (name "/LED_PAUSED") (class "Default")
      (node (ref "Q2") (pin "2") (pinfunction "G_2") (pintype "passive"))
      (node (ref "R27") (pin "2") (pinfunction "2_2") (pintype "passive"))
      (node (ref "U1") (pin "18") (pinfunction "PIO1_4/_ADC0_7/_SPI1_SSEL1/_SCT0_OUT7/_SPI0_MISO_18") (pintype "bidirectional"))
    )
    (net (code "5") (name "/LED_RUNNING") (class "Default")
      (node (ref "Q3") (pin "2") (pinfunction "G_2") (pintype "passive"))
      (node (ref "R28") (pin "2") (pinfunction "2_2") (pintype "passive"))
      (node (ref "U1") (pin "17") (pinfunction "PIO1_3/_ADC0_6/_SPI1_SSEL2/_SCT0_OUT6/_SPIO0_SCK_17") (pintype "bidirectional"))
    )
    (net (code "6") (name "/LED_STOPPED") (class "Default")
      (node (ref "Q1") (pin "2") (pinfunction "G_2") (pintype "passive"))
      (node (ref "R26") (pin "2") (pinfunction "2_2") (pintype "passive"))
      (node (ref "U1") (pin "16") (pinfunction "PIO1_2/_ADC0_5/_SPI1_SSEL3/_SCT0_OUT5_16") (pintype "bidirectional"))
    )
    (net (code "7") (name "/MIC_ADC") (class "Default")
      (node (ref "C37") (pin "2") (pinfunction "2_2") (pintype "passive"))
      (node (ref "R15") (pin "2") (pinfunction "2_2") (pintype "passive"))
      (node (ref "U1") (pin "19") (pinfunction "PIO1_5/_ADC0_8/_SPI1_SSEL0_19") (pintype "bidirectional"))
    )
    (net (code "8") (name "/MOTOR_IN1") (class "Default")
      (node (ref "U1") (pin "59") (pinfunction "PIO0_19/_U3_SCLK/_SCT0_OUT1_59") (pintype "bidirectional"))
      (node (ref "U6") (pin "3") (pinfunction "IN1_3") (pintype "input"))
    )
    (net (code "9") (name "/MOTOR_IN2") (class "Default")
      (node (ref "U1") (pin "58") (pinfunction "PIO0_18/_U3_TXD/_SCT0_OUT0_58") (pintype "bidirectional"))
      (node (ref "U6") (pin "2") (pinfunction "IN2_2") (pintype "input"))
    )
    (net (code "10") (name "/PAUSE_BUTTON") (class "Default")
      (node (ref "C49") (pin "2") (pinfunction "2_2") (pintype "passive"))
      (node (ref "R32") (pin "1") (pinfunction "1_1") (pintype "passive"))
      (node (ref "U1") (pin "14") (pinfunction "PIO1_0/_ADC0_3/_~{U2_RTS}_14") (pintype "bidirectional"))
    )
    (net (code "11") (name "/PLAY_BUTTON") (class "Default")
      (node (ref "C48") (pin "2") (pinfunction "2_2") (pintype "passive"))
      (node (ref "R31") (pin "1") (pinfunction "1_1") (pintype "passive"))
      (node (ref "U1") (pin "12") (pinfunction "PIO0_30/_ADC0_1/_SCT0_OUT3_12") (pintype "bidirectional"))
    )
    (net (code "12") (name "/POT_ADC") (class "Default")
      (node (ref "P3") (pin "2") (pinfunction "2_2") (pintype "passive"))
      (node (ref "U1") (pin "11") (pinfunction "PIO0_29/_ADC0_0/_SCT0_OUT2_11") (pintype "bidirectional"))
    )
    (net (code "13") (name "/RESET") (class "Default")
      (node (ref "C14") (pin "2") (pinfunction "2_2") (pintype "passive"))
      (node (ref "S2") (pin "2") (pinfunction "2_2") (pintype "passive"))
      (node (ref "SWD1") (pin "10") (pinfunction "~{RESET}_10") (pintype "input"))
      (node (ref "U1") (pin "64") (pinfunction "~{RESET}_64") (pintype "input"))
    )
    (net (code "14") (name "/RESTART_BUTTON") (class "Default")
      (node (ref "C50") (pin "2") (pinfunction "2_2") (pintype "passive"))
      (node (ref "R33") (pin "1") (pinfunction "1_1") (pintype "passive"))
      (node (ref "U1") (pin "15") (pinfunction "PIO1_1/_ADC0_4/_SCT0_OUT4_15") (pintype "bidirectional"))
    )
    (net (code "15") (name "/SPI_CLK") (class "Default")
      (node (ref "PM1") (pin "3") (pinfunction "CLK_3") (pintype "input"))
      (node (ref "U1") (pin "51") (pinfunction "PIO1_12/_U3_RXD/_SPI1_SCK_51") (pintype "bidirectional"))
    )
    (net (code "16") (name "/SPI_CS") (class "Default")
      (node (ref "PM1") (pin "7") (pinfunction "CS_7") (pintype "input"))
      (node (ref "U1") (pin "62") (pinfunction "PIO1_15/_SCT0_OUT5/_SPI1_SSEL0_62") (pintype "bidirectional"))
    )
    (net (code "17") (name "/SPI_DC") (class "Default")
      (node (ref "PM1") (pin "6") (pinfunction "DC_6") (pintype "input"))
      (node (ref "U1") (pin "60") (pinfunction "PIO0_20/_U3_RXD/_U0_SCLK_60") (pintype "bidirectional"))
    )
    (net (code "18") (name "/SPI_MOSI") (class "Default")
      (node (ref "PM1") (pin "4") (pinfunction "MOSI_4") (pintype "input"))
      (node (ref "U1") (pin "54") (pinfunction "PIO1_13/_U3_TXD/_SPI1_MOSI_54") (pintype "bidirectional"))
    )
    (net (code "19") (name "/SPI_RES") (class "Default")
      (node (ref "PM1") (pin "5") (pinfunction "RES_5") (pintype "input"))
      (node (ref "U1") (pin "57") (pinfunction "PIO1_14/_U2_RXD/_SCT0_OUT7/_SPI1_MISO_57") (pintype "bidirectional"))
    )
    (net (code "20") (name "/SWCLK") (class "Default")
      (node (ref "R17") (pin "1") (pinfunction "1_1") (pintype "passive"))
      (node (ref "SWD1") (pin "4") (pinfunction "SWCLK_4") (pintype "input"))
      (node (ref "U1") (pin "52") (pinfunction "SWCLK/_PIO_16_52") (pintype "bidirectional"))
    )
    (net (code "21") (name "/SWDIO") (class "Default")
      (node (ref "R16") (pin "1") (pinfunction "1_1") (pintype "passive"))
      (node (ref "SWD1") (pin "2") (pinfunction "SWDIO_2") (pintype "bidirectional"))
      (node (ref "U1") (pin "53") (pinfunction "SWDIO/_PIO_17_53") (pintype "bidirectional"))
    )
    (net (code "22") (name "/UART0_CTS") (class "Default")
      (node (ref "U1") (pin "36") (pinfunction "PIO0_2/_~{U0_CTS}_36") (pintype "bidirectional"))
      (node (ref "U7") (pin "2") (pinfunction "RTS#_2") (pintype "output"))
    )
    (net (code "23") (name "/UART0_RTS") (class "Default")
      (node (ref "U1") (pin "37") (pinfunction "PIO0_3/_~{U0_RTS}_37") (pintype "bidirectional"))
      (node (ref "U7") (pin "6") (pinfunction "CTS#_6") (pintype "input"))
    )
    (net (code "24") (name "/UART0_RX") (class "Default")
      (node (ref "U1") (pin "31") (pinfunction "PIO0_0/_U0_RXD/_SPI0_SSEL0/_SCT0_OUT3_31") (pintype "bidirectional"))
      (node (ref "U7") (pin "1") (pinfunction "TXD_1") (pintype "output"))
    )
    (net (code "25") (name "/UART0_TX") (class "Default")
      (node (ref "U1") (pin "32") (pinfunction "PIO0_1/_U0_TXD/_SPIO_SSEL1/_SCT0_OUT1_32") (pintype "bidirectional"))
      (node (ref "U7") (pin "4") (pinfunction "RXD_4") (pintype "input"))
    )
    (net (code "26") (name "/UP_BUTTON") (class "Default")
      (node (ref "C46") (pin "2") (pinfunction "2_2") (pintype "passive"))
      (node (ref "R29") (pin "1") (pinfunction "1_1") (pintype "passive"))
      (node (ref "U1") (pin "7") (pinfunction "PIO1_16/_SPI1_SSEL1_7") (pintype "bidirectional"))
    )
    (net (code "27") (name "/USB_ACTIVITY") (class "Default")
      (node (ref "R22") (pin "2") (pinfunction "2_2") (pintype "passive"))
      (node (ref "U7") (pin "16") (pinfunction "CBUS3_16") (pintype "bidirectional"))
    )
    (net (code "28") (name "/USB_DM") (class "Default")
      (node (ref "C45") (pin "2") (pinfunction "2_2") (pintype "passive"))
      (node (ref "P4") (pin "2") (pinfunction "USB_DM_2") (pintype "bidirectional"))
      (node (ref "R20") (pin "2") (pinfunction "2_2") (pintype "passive"))
    )
    (net (code "29") (name "/USB_DP") (class "Default")
      (node (ref "C44") (pin "2") (pinfunction "2_2") (pintype "passive"))
      (node (ref "P4") (pin "3") (pinfunction "USB_DP_3") (pintype "bidirectional"))
      (node (ref "R19") (pin "2") (pinfunction "2_2") (pintype "passive"))
    )
    (net (code "30") (name "GND") (class "Default")
      (node (ref "C1") (pin "1") (pinfunction "1_1") (pintype "passive"))
      (node (ref "C10") (pin "1") (pinfunction "1_1") (pintype "passive"))
      (node (ref "C11") (pin "1") (pinfunction "1_1") (pintype "passive"))
      (node (ref "C12") (pin "1") (pinfunction "1_1") (pintype "passive"))
      (node (ref "C13") (pin "1") (pinfunction "1_1") (pintype "passive"))
      (node (ref "C14") (pin "1") (pinfunction "1_1") (pintype "passive"))
      (node (ref "C15") (pin "1") (pinfunction "1_1") (pintype "passive"))
      (node (ref "C16") (pin "1") (pinfunction "1_1") (pintype "passive"))
      (node (ref "C17") (pin "1") (pinfunction "1_1") (pintype "passive"))
      (node (ref "C18") (pin "1") (pinfunction "1_1") (pintype "passive"))
      (node (ref "C19") (pin "1") (pinfunction "1_1") (pintype "passive"))
      (node (ref "C2") (pin "1") (pinfunction "1_1") (pintype "passive"))
      (node (ref "C20") (pin "1") (pinfunction "1_1") (pintype "passive"))
      (node (ref "C21") (pin "1") (pinfunction "1_1") (pintype "passive"))
      (node (ref "C22") (pin "1") (pinfunction "1_1") (pintype "passive"))
      (node (ref "C23") (pin "1") (pinfunction "1_1") (pintype "passive"))
      (node (ref "C26") (pin "1") (pinfunction "1_1") (pintype "passive"))
      (node (ref "C27") (pin "1") (pinfunction "1_1") (pintype "passive"))
      (node (ref "C28") (pin "1") (pinfunction "1_1") (pintype "passive"))
      (node (ref "C29") (pin "1") (pinfunction "1_1") (pintype "passive"))
      (node (ref "C3") (pin "1") (pinfunction "1_1") (pintype "passive"))
      (node (ref "C30") (pin "1") (pinfunction "1_1") (pintype "passive"))
      (node (ref "C33") (pin "1") (pinfunction "1_1") (pintype "passive"))
      (node (ref "C34") (pin "1") (pinfunction "1_1") (pintype "passive"))
      (node (ref "C37") (pin "1") (pinfunction "1_1") (pintype "passive"))
      (node (ref "C38") (pin "1") (pinfunction "1_1") (pintype "passive"))
      (node (ref "C39") (pin "1") (pinfunction "1_1") (pintype "passive"))
      (node (ref "C4") (pin "1") (pinfunction "1_1") (pintype "passive"))
      (node (ref "C40") (pin "1") (pinfunction "1_1") (pintype "passive"))
      (node (ref "C41") (pin "1") (pinfunction "1_1") (pintype "passive"))
      (node (ref "C42") (pin "1") (pinfunction "1_1") (pintype "passive"))
      (node (ref "C43") (pin "1") (pinfunction "1_1") (pintype "passive"))
      (node (ref "C44") (pin "1") (pinfunction "1_1") (pintype "passive"))
      (node (ref "C45") (pin "1") (pinfunction "1_1") (pintype "passive"))
      (node (ref "C46") (pin "1") (pinfunction "1_1") (pintype "passive"))
      (node (ref "C47") (pin "1") (pinfunction "1_1") (pintype "passive"))
      (node (ref "C48") (pin "1") (pinfunction "1_1") (pintype "passive"))
      (node (ref "C49") (pin "1") (pinfunction "1_1") (pintype "passive"))
      (node (ref "C5") (pin "1") (pinfunction "1_1") (pintype "passive"))
      (node (ref "C50") (pin "1") (pinfunction "1_1") (pintype "passive"))
      (node (ref "C6") (pin "1") (pinfunction "1_1") (pintype "passive"))
      (node (ref "C7") (pin "1") (pinfunction "1_1") (pintype "passive"))
      (node (ref "C8") (pin "1") (pinfunction "1_1") (pintype "passive"))
      (node (ref "C9") (pin "1") (pinfunction "1_1") (pintype "passive"))
      (node (ref "D2") (pin "1") (pinfunction "A_1") (pintype "passive"))
      (node (ref "D3") (pin "1") (pinfunction "A_1") (pintype "passive"))
      (node (ref "MK1") (pin "1") (pinfunction "1_1") (pintype "passive"))
      (node (ref "P1") (pin "1") (pinfunction "1_1") (pintype "passive"))
      (node (ref "P3") (pin "3") (pinfunction "3_3") (pintype "passive"))
      (node (ref "P4") (pin "5") (pinfunction "GND_5") (pintype "power_in"))
      (node (ref "PM1") (pin "1") (pinfunction "GND_1") (pintype "power_in"))
      (node (ref "Q1") (pin "3") (pinfunction "S_3") (pintype "passive"))
      (node (ref "Q2") (pin "3") (pinfunction "S_3") (pintype "passive"))
      (node (ref "Q3") (pin "3") (pinfunction "S_3") (pintype "passive"))
      (node (ref "R11") (pin "1") (pinfunction "1_1") (pintype "passive"))
      (node (ref "R18") (pin "1") (pinfunction "1_1") (pintype "passive"))
      (node (ref "R2") (pin "1") (pinfunction "1_1") (pintype "passive"))
      (node (ref "R26") (pin "1") (pinfunction "1_1") (pintype "passive"))
      (node (ref "R27") (pin "1") (pinfunction "1_1") (pintype "passive"))
      (node (ref "R28") (pin "1") (pinfunction "1_1") (pintype "passive"))
      (node (ref "R34") (pin "1") (pinfunction "1_1") (pintype "passive"))
      (node (ref "R4") (pin "1") (pinfunction "1_1") (pintype "passive"))
      (node (ref "R5") (pin "2") (pinfunction "2_2") (pintype "passive"))
      (node (ref "R6") (pin "1") (pinfunction "1_1") (pintype "passive"))
      (node (ref "R7") (pin "1") (pinfunction "1_1") (pintype "passive"))
      (node (ref "Rp") (pin "1") (pinfunction "1_1") (pintype "passive"))
      (node (ref "S2") (pin "1") (pinfunction "1_1") (pintype "passive"))
      (node (ref "S3") (pin "1") (pinfunction "1_1") (pintype "passive"))
      (node (ref "S4") (pin "1") (pinfunction "1_1") (pintype "passive"))
      (node (ref "S5") (pin "1") (pinfunction "1_1") (pintype "passive"))
      (node (ref "S6") (pin "1") (pinfunction "1_1") (pintype "passive"))
      (node (ref "S7") (pin "1") (pinfunction "1_1") (pintype "passive"))
      (node (ref "SWD1") (pin "3") (pinfunction "GND_3") (pintype "power_in"))
      (node (ref "SWD1") (pin "5") (pinfunction "GND_5") (pintype "power_in"))
      (node (ref "SWD1") (pin "9") (pinfunction "GND_9") (pintype "tri_state"))
      (node (ref "U1") (pin "20") (pinfunction "VSSA_20") (pintype "power_in"))
      (node (ref "U1") (pin "21") (pinfunction "VREFN_21") (pintype "input"))
      (node (ref "U1") (pin "25") (pinfunction "VSS_25") (pintype "power_in"))
      (node (ref "U1") (pin "33") (pinfunction "RTCIN_33") (pintype "input"))
      (node (ref "U1") (pin "55") (pinfunction "VSS_55") (pintype "power_in"))
      (node (ref "U1") (pin "9") (pinfunction "VSS_9") (pintype "power_in"))
      (node (ref "U2") (pin "2") (pinfunction "GND_2") (pintype "power_in"))
      (node (ref "U3") (pin "1") (pinfunction "GND_1") (pintype "power_in"))
      (node (ref "U4") (pin "1") (pinfunction "GND_1") (pintype "power_in"))
      (node (ref "U5") (pin "4") (pinfunction "VCC+_4") (pintype "power_in"))
      (node (ref "U6") (pin "1") (pinfunction "GND_1") (pintype "power_in"))
      (node (ref "U6") (pin "7") (pinfunction "PGND_7") (pintype "power_in"))
      (node (ref "U6") (pin "9") (pinfunction "PAD_9") (pintype "power_in"))
      (node (ref "U7") (pin "13") (pinfunction "GND_13") (pintype "power_in"))
      (node (ref "U7") (pin "5") (pinfunction "GND_5") (pintype "power_in"))
      (node (ref "Y1") (pin "2") (pinfunction "GND_2") (pintype "power_in"))
      (node (ref "Y1") (pin "4") (pinfunction "GND_4") (pintype "power_in"))
    )
    (net (code "31") (name "Net-(C35-Pad1)") (class "Default")
      (node (ref "C35") (pin "1") (pinfunction "1_1") (pintype "passive"))
      (node (ref "R9") (pin "1") (pinfunction "1_1") (pintype "passive"))
    )
    (net (code "32") (name "Net-(C35-Pad2)") (class "Default")
      (node (ref "C35") (pin "2") (pinfunction "2_2") (pintype "passive"))
      (node (ref "MK1") (pin "2") (pinfunction "2_2") (pintype "passive"))
      (node (ref "R8") (pin "1") (pinfunction "1_1") (pintype "passive"))
    )
    (net (code "33") (name "Net-(D1-A)") (class "Default")
      (node (ref "D1") (pin "1") (pinfunction "A_1") (pintype "passive"))
      (node (ref "S1") (pin "2") (pinfunction "2_2") (pintype "passive"))
    )
    (net (code "34") (name "Net-(D4-K)") (class "Default")
      (node (ref "D4") (pin "2") (pinfunction "K_2") (pintype "passive"))
      (node (ref "R5") (pin "1") (pinfunction "1_1") (pintype "passive"))
    )
    (net (code "35") (name "Net-(D5-K)") (class "Default")
      (node (ref "D5") (pin "2") (pinfunction "K_2") (pintype "passive"))
      (node (ref "R6") (pin "2") (pinfunction "2_2") (pintype "passive"))
    )
    (net (code "36") (name "Net-(D6-K)") (class "Default")
      (node (ref "D6") (pin "2") (pinfunction "K_2") (pintype "passive"))
      (node (ref "R7") (pin "2") (pinfunction "2_2") (pintype "passive"))
    )
    (net (code "37") (name "Net-(D7-A)") (class "Default")
      (node (ref "C41") (pin "2") (pinfunction "2_2") (pintype "passive"))
      (node (ref "C42") (pin "2") (pinfunction "2_2") (pintype "passive"))
      (node (ref "D7") (pin "1") (pinfunction "A_1") (pintype "passive"))
      (node (ref "D8") (pin "1") (pinfunction "A_1") (pintype "passive"))
      (node (ref "L3") (pin "2") (pinfunction "2_2") (pintype "passive"))
      (node (ref "U7") (pin "12") (pinfunction "VCC_12") (pintype "power_in"))
    )
    (net (code "38") (name "Net-(D7-K)") (class "Default")
      (node (ref "D7") (pin "2") (pinfunction "K_2") (pintype "passive"))
      (node (ref "R22") (pin "1") (pinfunction "1_1") (pintype "passive"))
    )
    (net (code "39") (name "Net-(D8-K)") (class "Default")
      (node (ref "D8") (pin "2") (pinfunction "K_2") (pintype "passive"))
      (node (ref "R34") (pin "2") (pinfunction "2_2") (pintype "passive"))
    )
    (net (code "40") (name "Net-(D9-K)") (class "Default")
      (node (ref "D9") (pin "2") (pinfunction "K_2") (pintype "passive"))
      (node (ref "R23") (pin "2") (pinfunction "2_2") (pintype "passive"))
    )
    (net (code "41") (name "Net-(D10-K)") (class "Default")
      (node (ref "D10") (pin "2") (pinfunction "K_2") (pintype "passive"))
      (node (ref "R24") (pin "2") (pinfunction "2_2") (pintype "passive"))
    )
    (net (code "42") (name "Net-(D11-K)") (class "Default")
      (node (ref "D11") (pin "2") (pinfunction "K_2") (pintype "passive"))
      (node (ref "R25") (pin "2") (pinfunction "2_2") (pintype "passive"))
    )
    (net (code "43") (name "Net-(P1-Pad2)") (class "Default")
      (node (ref "P1") (pin "2") (pinfunction "2_2") (pintype "passive"))
      (node (ref "S1") (pin "1") (pinfunction "1_1") (pintype "passive"))
    )
    (net (code "44") (name "Net-(P4-VUSB)") (class "Default")
      (node (ref "C40") (pin "2") (pinfunction "2_2") (pintype "passive"))
      (node (ref "L3") (pin "1") (pinfunction "1_1") (pintype "passive"))
      (node (ref "P4") (pin "1") (pinfunction "VUSB_1") (pintype "power_in"))
    )
    (net (code "45") (name "Net-(Q1-D)") (class "Default")
      (node (ref "Q1") (pin "1") (pinfunction "D_1") (pintype "passive"))
      (node (ref "R23") (pin "1") (pinfunction "1_1") (pintype "passive"))
    )
    (net (code "46") (name "Net-(Q2-D)") (class "Default")
      (node (ref "Q2") (pin "1") (pinfunction "D_1") (pintype "passive"))
      (node (ref "R24") (pin "1") (pinfunction "1_1") (pintype "passive"))
    )
    (net (code "47") (name "Net-(Q3-D)") (class "Default")
      (node (ref "Q3") (pin "1") (pinfunction "D_1") (pintype "passive"))
      (node (ref "R25") (pin "1") (pinfunction "1_1") (pintype "passive"))
    )
    (net (code "48") (name "Net-(R14-BOT)") (class "Default")
      (node (ref "R14") (pin "2") (pinfunction "BOT_2") (pintype "passive"))
      (node (ref "R14") (pin "3") (pinfunction "TAP_3") (pintype "passive"))
      (node (ref "R15") (pin "1") (pinfunction "1_1") (pintype "passive"))
      (node (ref "U5") (pin "1") (pinfunction "OUT1_1") (pintype "output"))
    )
    (net (code "49") (name "Net-(R14-TOP)") (class "Default")
      (node (ref "R13") (pin "2") (pinfunction "2_2") (pintype "passive"))
      (node (ref "R14") (pin "1") (pinfunction "TOP_1") (pintype "passive"))
      (node (ref "U5") (pin "2") (pinfunction "IN1-_2") (pintype "input"))
    )
    (net (code "50") (name "Net-(R29-Pad2)") (class "Default")
      (node (ref "R29") (pin "2") (pinfunction "2_2") (pintype "passive"))
      (node (ref "S3") (pin "2") (pinfunction "2_2") (pintype "passive"))
    )
    (net (code "51") (name "Net-(R30-Pad2)") (class "Default")
      (node (ref "R30") (pin "2") (pinfunction "2_2") (pintype "passive"))
      (node (ref "S4") (pin "2") (pinfunction "2_2") (pintype "passive"))
    )
    (net (code "52") (name "Net-(R31-Pad2)") (class "Default")
      (node (ref "R31") (pin "2") (pinfunction "2_2") (pintype "passive"))
      (node (ref "S5") (pin "2") (pinfunction "2_2") (pintype "passive"))
    )
    (net (code "53") (name "Net-(R32-Pad2)") (class "Default")
      (node (ref "R32") (pin "2") (pinfunction "2_2") (pintype "passive"))
      (node (ref "S6") (pin "2") (pinfunction "2_2") (pintype "passive"))
    )
    (net (code "54") (name "Net-(R33-Pad2)") (class "Default")
      (node (ref "R33") (pin "2") (pinfunction "2_2") (pintype "passive"))
      (node (ref "S7") (pin "2") (pinfunction "2_2") (pintype "passive"))
    )
    (net (code "55") (name "Net-(U2-X1)") (class "Default")
      (node (ref "C15") (pin "2") (pinfunction "2_2") (pintype "passive"))
      (node (ref "RF") (pin "1") (pinfunction "1_1") (pintype "passive"))
      (node (ref "U2") (pin "3") (pinfunction "X1_3") (pintype "input"))
      (node (ref "Y1") (pin "1") (pinfunction "OSC1_1") (pintype "passive"))
    )
    (net (code "56") (name "Net-(U2-X2)") (class "Default")
      (node (ref "RF") (pin "2") (pinfunction "2_2") (pintype "passive"))
      (node (ref "Rs") (pin "2") (pinfunction "2_2") (pintype "passive"))
      (node (ref "U2") (pin "4") (pinfunction "X2_4") (pintype "output"))
    )
    (net (code "57") (name "Net-(U3-EN)") (class "Default")
      (node (ref "Ren1") (pin "1") (pinfunction "1_1") (pintype "passive"))
      (node (ref "U3") (pin "5") (pinfunction "EN_5") (pintype "input"))
    )
    (net (code "58") (name "Net-(U3-SW)") (class "Default")
      (node (ref "C24") (pin "2") (pinfunction "2_2") (pintype "passive"))
      (node (ref "L1") (pin "2") (pinfunction "2_2") (pintype "passive"))
      (node (ref "U3") (pin "2") (pinfunction "SW_2") (pintype "output"))
    )
    (net (code "59") (name "Net-(U3-VBST)") (class "Default")
      (node (ref "C24") (pin "1") (pinfunction "1_1") (pintype "passive"))
      (node (ref "U3") (pin "6") (pinfunction "VBST_6") (pintype "input"))
    )
    (net (code "60") (name "Net-(U3-VFB)") (class "Default")
      (node (ref "C25") (pin "2") (pinfunction "2_2") (pintype "passive"))
      (node (ref "R1") (pin "1") (pinfunction "1_1") (pintype "passive"))
      (node (ref "R2") (pin "2") (pinfunction "2_2") (pintype "passive"))
      (node (ref "U3") (pin "4") (pinfunction "VFB_4") (pintype "input"))
    )
    (net (code "61") (name "Net-(U4-EN)") (class "Default")
      (node (ref "Ren2") (pin "1") (pinfunction "1_1") (pintype "passive"))
      (node (ref "U4") (pin "5") (pinfunction "EN_5") (pintype "input"))
    )
    (net (code "62") (name "Net-(U4-SW)") (class "Default")
      (node (ref "C31") (pin "2") (pinfunction "2_2") (pintype "passive"))
      (node (ref "L2") (pin "2") (pinfunction "2_2") (pintype "passive"))
      (node (ref "U4") (pin "2") (pinfunction "SW_2") (pintype "output"))
    )
    (net (code "63") (name "Net-(U4-VBST)") (class "Default")
      (node (ref "C31") (pin "1") (pinfunction "1_1") (pintype "passive"))
      (node (ref "U4") (pin "6") (pinfunction "VBST_6") (pintype "input"))
    )
    (net (code "64") (name "Net-(U4-VFB)") (class "Default")
      (node (ref "C32") (pin "2") (pinfunction "2_2") (pintype "passive"))
      (node (ref "R3") (pin "1") (pinfunction "1_1") (pintype "passive"))
      (node (ref "R4") (pin "2") (pinfunction "2_2") (pintype "passive"))
      (node (ref "U4") (pin "4") (pinfunction "VFB_4") (pintype "input"))
    )
    (net (code "65") (name "Net-(U5A-IN1+)") (class "Default")
      (node (ref "R10") (pin "1") (pinfunction "1_1") (pintype "passive"))
      (node (ref "R11") (pin "2") (pinfunction "2_2") (pintype "passive"))
      (node (ref "U5") (pin "3") (pinfunction "IN1+_3") (pintype "input"))
      (node (ref "U5") (pin "5") (pinfunction "IN2+_5") (pintype "input"))
    )
    (net (code "66") (name "Net-(U5B-IN2-)") (class "Default")
      (node (ref "C36") (pin "2") (pinfunction "2_2") (pintype "passive"))
      (node (ref "R12") (pin "1") (pinfunction "1_1") (pintype "passive"))
      (node (ref "R9") (pin "2") (pinfunction "2_2") (pintype "passive"))
      (node (ref "U5") (pin "6") (pinfunction "IN2-_6") (pintype "input"))
    )
    (net (code "67") (name "Net-(U5B-OUT2)") (class "Default")
      (node (ref "C36") (pin "1") (pinfunction "1_1") (pintype "passive"))
      (node (ref "R12") (pin "2") (pinfunction "2_2") (pintype "passive"))
      (node (ref "R13") (pin "1") (pinfunction "1_1") (pintype "passive"))
      (node (ref "U5") (pin "7") (pinfunction "OUT2_7") (pintype "output"))
    )
    (net (code "68") (name "Net-(U6-ILIM)") (class "Default")
      (node (ref "R18") (pin "2") (pinfunction "2_2") (pintype "passive"))
      (node (ref "U6") (pin "4") (pinfunction "ILIM_4") (pintype "input"))
    )
    (net (code "69") (name "Net-(U6-OUT1)") (class "Default")
      (node (ref "P2") (pin "1") (pinfunction "1_1") (pintype "passive"))
      (node (ref "U6") (pin "6") (pinfunction "OUT1_6") (pintype "output"))
    )
    (net (code "70") (name "Net-(U6-OUT2)") (class "Default")
      (node (ref "P2") (pin "2") (pinfunction "2_2") (pintype "passive"))
      (node (ref "U6") (pin "8") (pinfunction "OUT2_8") (pintype "output"))
    )
    (net (code "71") (name "Net-(U7-3V3OUT)") (class "Default")
      (node (ref "C43") (pin "2") (pinfunction "2_2") (pintype "passive"))
      (node (ref "U7") (pin "10") (pinfunction "3V3OUT_10") (pintype "power_in"))
      (node (ref "U7") (pin "11") (pinfunction "RESET#_11") (pintype "input"))
      (node (ref "U7") (pin "3") (pinfunction "VCCIO_3") (pintype "power_in"))
    )
    (net (code "72") (name "Net-(U7-USBDM)") (class "Default")
      (node (ref "R20") (pin "1") (pinfunction "1_1") (pintype "passive"))
      (node (ref "U7") (pin "9") (pinfunction "USBDM_9") (pintype "input"))
    )
    (net (code "73") (name "Net-(U7-USBDP)") (class "Default")
      (node (ref "R19") (pin "1") (pinfunction "1_1") (pintype "passive"))
      (node (ref "U7") (pin "8") (pinfunction "USBDP_8") (pintype "input"))
    )
    (net (code "74") (name "Net-(Y1-OSC2)") (class "Default")
      (node (ref "C16") (pin "2") (pinfunction "2_2") (pintype "passive"))
      (node (ref "Rs") (pin "1") (pinfunction "1_1") (pintype "passive"))
      (node (ref "Y1") (pin "3") (pinfunction "OSC2_3") (pintype "passive"))
    )
    (net (code "75") (name "V3.3") (class "Default")
      (node (ref "C1") (pin "2") (pinfunction "2_2") (pintype "passive"))
      (node (ref "C10") (pin "2") (pinfunction "2_2") (pintype "passive"))
      (node (ref "C11") (pin "2") (pinfunction "2_2") (pintype "passive"))
      (node (ref "C12") (pin "2") (pinfunction "2_2") (pintype "passive"))
      (node (ref "C13") (pin "2") (pinfunction "2_2") (pintype "passive"))
      (node (ref "C2") (pin "2") (pinfunction "2_2") (pintype "passive"))
      (node (ref "C22") (pin "2") (pinfunction "2_2") (pintype "passive"))
      (node (ref "C23") (pin "2") (pinfunction "2_2") (pintype "passive"))
      (node (ref "C25") (pin "1") (pinfunction "1_1") (pintype "passive"))
      (node (ref "C3") (pin "2") (pinfunction "2_2") (pintype "passive"))
      (node (ref "C33") (pin "2") (pinfunction "2_2") (pintype "passive"))
      (node (ref "C34") (pin "2") (pinfunction "2_2") (pintype "passive"))
      (node (ref "C4") (pin "2") (pinfunction "2_2") (pintype "passive"))
      (node (ref "C5") (pin "2") (pinfunction "2_2") (pintype "passive"))
      (node (ref "C6") (pin "2") (pinfunction "2_2") (pintype "passive"))
      (node (ref "C7") (pin "2") (pinfunction "2_2") (pintype "passive"))
      (node (ref "C8") (pin "2") (pinfunction "2_2") (pintype "passive"))
      (node (ref "C9") (pin "2") (pinfunction "2_2") (pintype "passive"))
      (node (ref "D10") (pin "1") (pinfunction "A_1") (pintype "passive"))
      (node (ref "D11") (pin "1") (pinfunction "A_1") (pintype "passive"))
      (node (ref "D3") (pin "2") (pinfunction "K_2") (pintype "passive"))
      (node (ref "D6") (pin "1") (pinfunction "A_1") (pintype "passive"))
      (node (ref "D9") (pin "1") (pinfunction "A_1") (pintype "passive"))
      (node (ref "L1") (pin "1") (pinfunction "1_1") (pintype "passive"))
      (node (ref "P3") (pin "1") (pinfunction "1_1") (pintype "passive"))
      (node (ref "PM1") (pin "2") (pinfunction "VCC_2") (pintype "power_in"))
      (node (ref "R1") (pin "2") (pinfunction "2_2") (pintype "passive"))
      (node (ref "R10") (pin "2") (pinfunction "2_2") (pintype "passive"))
      (node (ref "R16") (pin "2") (pinfunction "2_2") (pintype "passive"))
      (node (ref "R17") (pin "2") (pinfunction "2_2") (pintype "passive"))
      (node (ref "R8") (pin "2") (pinfunction "2_2") (pintype "passive"))
      (node (ref "SWD1") (pin "1") (pinfunction "VDD_1") (pintype "power_in"))
      (node (ref "U1") (pin "22") (pinfunction "VREFP_22") (pintype "input"))
      (node (ref "U1") (pin "23") (pinfunction "VDDA_23") (pintype "power_in"))
      (node (ref "U1") (pin "24") (pinfunction "VDD_24") (pintype "power_in"))
      (node (ref "U1") (pin "34") (pinfunction "VDD_34") (pintype "power_in"))
      (node (ref "U1") (pin "56") (pinfunction "VDD_56") (pintype "power_in"))
      (node (ref "U1") (pin "8") (pinfunction "VDD_8") (pintype "power_in"))
      (node (ref "U2") (pin "5") (pinfunction "VCC_5") (pintype "power_in"))
      (node (ref "U5") (pin "8") (pinfunction "VCC-_8") (pintype "power_in"))
    )
    (net (code "76") (name "V6.5") (class "Default")
      (node (ref "C29") (pin "2") (pinfunction "2_2") (pintype "passive"))
      (node (ref "C30") (pin "2") (pinfunction "2_2") (pintype "passive"))
      (node (ref "C32") (pin "1") (pinfunction "1_1") (pintype "passive"))
      (node (ref "C38") (pin "2") (pinfunction "2_2") (pintype "passive"))
      (node (ref "C39") (pin "2") (pinfunction "2_2") (pintype "passive"))
      (node (ref "D5") (pin "1") (pinfunction "A_1") (pintype "passive"))
      (node (ref "L2") (pin "1") (pinfunction "1_1") (pintype "passive"))
      (node (ref "R3") (pin "2") (pinfunction "2_2") (pintype "passive"))
      (node (ref "U6") (pin "5") (pinfunction "VM_5") (pintype "power_in"))
    )
    (net (code "77") (name "VIN") (class "Default")
      (node (ref "C17") (pin "2") (pinfunction "2_2") (pintype "passive"))
      (node (ref "C18") (pin "2") (pinfunction "2_2") (pintype "passive"))
      (node (ref "C19") (pin "2") (pinfunction "2_2") (pintype "passive"))
      (node (ref "C20") (pin "2") (pinfunction "2_2") (pintype "passive"))
      (node (ref "C21") (pin "2") (pinfunction "2_2") (pintype "passive"))
      (node (ref "C26") (pin "2") (pinfunction "2_2") (pintype "passive"))
      (node (ref "C27") (pin "2") (pinfunction "2_2") (pintype "passive"))
      (node (ref "C28") (pin "2") (pinfunction "2_2") (pintype "passive"))
      (node (ref "D1") (pin "2") (pinfunction "K_2") (pintype "passive"))
      (node (ref "D2") (pin "2") (pinfunction "K_2") (pintype "passive"))
      (node (ref "D4") (pin "1") (pinfunction "A_1") (pintype "passive"))
      (node (ref "Ren1") (pin "2") (pinfunction "2_2") (pintype "passive"))
      (node (ref "U3") (pin "3") (pinfunction "VIN_3") (pintype "power_in"))
      (node (ref "U4") (pin "3") (pinfunction "VIN_3") (pintype "power_in"))
    )
    (net (code "78") (name "unconnected-(S1-Pad3)") (class "Default")
      (node (ref "S1") (pin "3") (pinfunction "3_3") (pintype "passive"))
    )
    (net (code "79") (name "unconnected-(SWD1-NC-Pad6)") (class "Default")
      (node (ref "SWD1") (pin "6") (pinfunction "NC_6") (pintype "passive"))
    )
    (net (code "80") (name "unconnected-(SWD1-NC-Pad7)") (class "Default")
      (node (ref "SWD1") (pin "7") (pinfunction "NC_7") (pintype "passive"))
    )
    (net (code "81") (name "unconnected-(SWD1-NC-Pad8)") (class "Default")
      (node (ref "SWD1") (pin "8") (pinfunction "NC_8") (pintype "passive"))
    )
    (net (code "82") (name "unconnected-(U1-PIO0_4{slash}_U0_SCLK{slash}_SPIO0_SSEL2-Pad38)") (class "Default")
      (node (ref "U1") (pin "38") (pinfunction "PIO0_4/_U0_SCLK/_SPIO0_SSEL2_38") (pintype "bidirectional"))
    )
    (net (code "83") (name "unconnected-(U1-PIO0_5{slash}_U1_RXD{slash}_SCT0_OUT6-Pad39)") (class "Default")
      (node (ref "U1") (pin "39") (pinfunction "PIO0_5/_U1_RXD/_SCT0_OUT6_39") (pintype "bidirectional"))
    )
    (net (code "84") (name "unconnected-(U1-PIO0_6{slash}_U1_TXD-Pad40)") (class "Default")
      (node (ref "U1") (pin "40") (pinfunction "PIO0_6/_U1_TXD_40") (pintype "bidirectional"))
    )
    (net (code "85") (name "unconnected-(U1-PIO0_7{slash}_U1_SCLK{slash}_SCT0_OUT0-Pad41)") (class "Default")
      (node (ref "U1") (pin "41") (pinfunction "PIO0_7/_U1_SCLK/_SCT0_OUT0_41") (pintype "bidirectional"))
    )
    (net (code "86") (name "unconnected-(U1-PIO0_8{slash}_U2_RXD{slash}_SCT0_OUT1-Pad43)") (class "Default")
      (node (ref "U1") (pin "43") (pinfunction "PIO0_8/_U2_RXD/_SCT0_OUT1_43") (pintype "bidirectional"))
    )
    (net (code "87") (name "unconnected-(U1-PIO0_9{slash}_U2_TXD{slash}_SCT0_OUT2{slash}_SPI0_SSEL0-Pad44)") (class "Default")
      (node (ref "U1") (pin "44") (pinfunction "PIO0_9/_U2_TXD/_SCT0_OUT2/_SPI0_SSEL0_44") (pintype "bidirectional"))
    )
    (net (code "88") (name "unconnected-(U1-PIO0_10{slash}_U2_SCLK{slash}_SCT0_OUT3-Pad45)") (class "Default")
      (node (ref "U1") (pin "45") (pinfunction "PIO0_10/_U2_SCLK/_SCT0_OUT3_45") (pintype "bidirectional"))
    )
    (net (code "89") (name "unconnected-(U1-PIO0_11{slash}_SPI0_SCK{slash}_U1_RXD-Pad46)") (class "Default")
      (node (ref "U1") (pin "46") (pinfunction "PIO0_11/_SPI0_SCK/_U1_RXD_46") (pintype "bidirectional"))
    )
    (net (code "90") (name "unconnected-(U1-PIO0_12{slash}_SPI0_MOSI{slash}_U1_TXD-Pad47)") (class "Default")
      (node (ref "U1") (pin "47") (pinfunction "PIO0_12/_SPI0_MOSI/_U1_TXD_47") (pintype "bidirectional"))
    )
    (net (code "91") (name "unconnected-(U1-PIO0_13{slash}_SPI0_MISO{slash}_SCT0_OUT4-Pad48)") (class "Default")
      (node (ref "U1") (pin "48") (pinfunction "PIO0_13/_SPI0_MISO/_SCT0_OUT4_48") (pintype "bidirectional"))
    )
    (net (code "92") (name "unconnected-(U1-PIO0_15{slash}_SPI0_SSEL1-Pad50)") (class "Default")
      (node (ref "U1") (pin "50") (pinfunction "PIO0_15/_SPI0_SSEL1_50") (pintype "bidirectional"))
    )
    (net (code "93") (name "unconnected-(U1-PIO0_21{slash}_CLKOUT{slash}_U0_TXD-Pad61)") (class "Default")
      (node (ref "U1") (pin "61") (pinfunction "PIO0_21/_CLKOUT/_U0_TXD_61") (pintype "bidirectional"))
    )
    (net (code "94") (name "unconnected-(U1-PIO0_23{slash}_I2C0_SCL-Pad1)") (class "Default")
      (node (ref "U1") (pin "1") (pinfunction "PIO0_23/_I2C0_SCL_1") (pintype "bidirectional"))
    )
    (net (code "95") (name "unconnected-(U1-PIO0_24{slash}_I2C0_SDA-Pad2)") (class "Default")
      (node (ref "U1") (pin "2") (pinfunction "PIO0_24/_I2C0_SDA_2") (pintype "bidirectional"))
    )
    (net (code "96") (name "unconnected-(U1-PIO0_25{slash}_I2C1_SCL{slash}_~{U1_CTS}-Pad3)") (class "Default")
      (node (ref "U1") (pin "3") (pinfunction "PIO0_25/_I2C1_SCL/_~{U1_CTS}_3") (pintype "bidirectional"))
    )
    (net (code "97") (name "unconnected-(U1-PIO0_26{slash}_I2C1_SDA-Pad4)") (class "Default")
      (node (ref "U1") (pin "4") (pinfunction "PIO0_26/_I2C1_SDA_4") (pintype "bidirectional"))
    )
    (net (code "98") (name "unconnected-(U1-PIO0_27{slash}_I2C_SCL-Pad5)") (class "Default")
      (node (ref "U1") (pin "5") (pinfunction "PIO0_27/_I2C_SCL_5") (pintype "bidirectional"))
    )
    (net (code "99") (name "unconnected-(U1-PIO0_28{slash}_I2C2_SDA-Pad6)") (class "Default")
      (node (ref "U1") (pin "6") (pinfunction "PIO0_28/_I2C2_SDA_6") (pintype "bidirectional"))
    )
    (net (code "100") (name "unconnected-(U1-PIO0_31{slash}_ADC0_2{slash}_~{U2_CTS}{slash}_ISP-Pad13)") (class "Default")
      (node (ref "U1") (pin "13") (pinfunction "PIO0_31/_ADC0_2/_~{U2_CTS}/_ISP_13") (pintype "bidirectional+no_connect"))
    )
    (net (code "101") (name "unconnected-(U1-PIO1_6{slash}_ADC0_9{slash}_SPI1_SCK-Pad26)") (class "Default")
      (node (ref "U1") (pin "26") (pinfunction "PIO1_6/_ADC0_9/_SPI1_SCK_26") (pintype "bidirectional"))
    )
    (net (code "102") (name "unconnected-(U1-PIO1_7{slash}_ADC0_10{slash}_SPI1_MOSI-Pad27)") (class "Default")
      (node (ref "U1") (pin "27") (pinfunction "PIO1_7/_ADC0_10/_SPI1_MOSI_27") (pintype "bidirectional"))
    )
    (net (code "103") (name "unconnected-(U1-PIO1_8{slash}_ADC0_11{slash}_SPI1_MISO-Pad28)") (class "Default")
      (node (ref "U1") (pin "28") (pinfunction "PIO1_8/_ADC0_11/_SPI1_MISO_28") (pintype "bidirectional"))
    )
    (net (code "104") (name "unconnected-(U1-PIO1_9{slash}_SPI0_MOSI-Pad29)") (class "Default")
      (node (ref "U1") (pin "29") (pinfunction "PIO1_9/_SPI0_MOSI_29") (pintype "bidirectional"))
    )
    (net (code "105") (name "unconnected-(U1-PIO1_10{slash}_U1_TXD{slash}_SCT_OUT4-Pad30)") (class "Default")
      (node (ref "U1") (pin "30") (pinfunction "PIO1_10/_U1_TXD/_SCT_OUT4_30") (pintype "bidirectional"))
    )
    (net (code "106") (name "unconnected-(U1-PIO1_11{slash}_~{U1_RTS}-Pad42)") (class "Default")
      (node (ref "U1") (pin "42") (pinfunction "PIO1_11/_~{U1_RTS}_42") (pintype "bidirectional"))
    )
    (net (code "107") (name "unconnected-(U1-RTCOUT-Pad35)") (class "Default")
      (node (ref "U1") (pin "35") (pinfunction "RTCOUT_35") (pintype "output"))
    )
    (net (code "108") (name "unconnected-(U2-NC-Pad1)") (class "Default")
      (node (ref "U2") (pin "1") (pinfunction "NC_1") (pintype "passive"))
    )
    (net (code "109") (name "unconnected-(U7-CBUS0-Pad15)") (class "Default")
      (node (ref "U7") (pin "15") (pinfunction "CBUS0_15") (pintype "bidirectional"))
    )
    (net (code "110") (name "unconnected-(U7-CBUS1-Pad14)") (class "Default")
      (node (ref "U7") (pin "14") (pinfunction "CBUS1_14") (pintype "bidirectional"))
    )
    (net (code "111") (name "unconnected-(U7-CBUS2-Pad7)") (class "Default")
      (node (ref "U7") (pin "7") (pinfunction "CBUS2_7") (pintype "bidirectional"))
    )
  )
)
